# shield.net
KiCad netlist of a schematic drawn in EAGLE
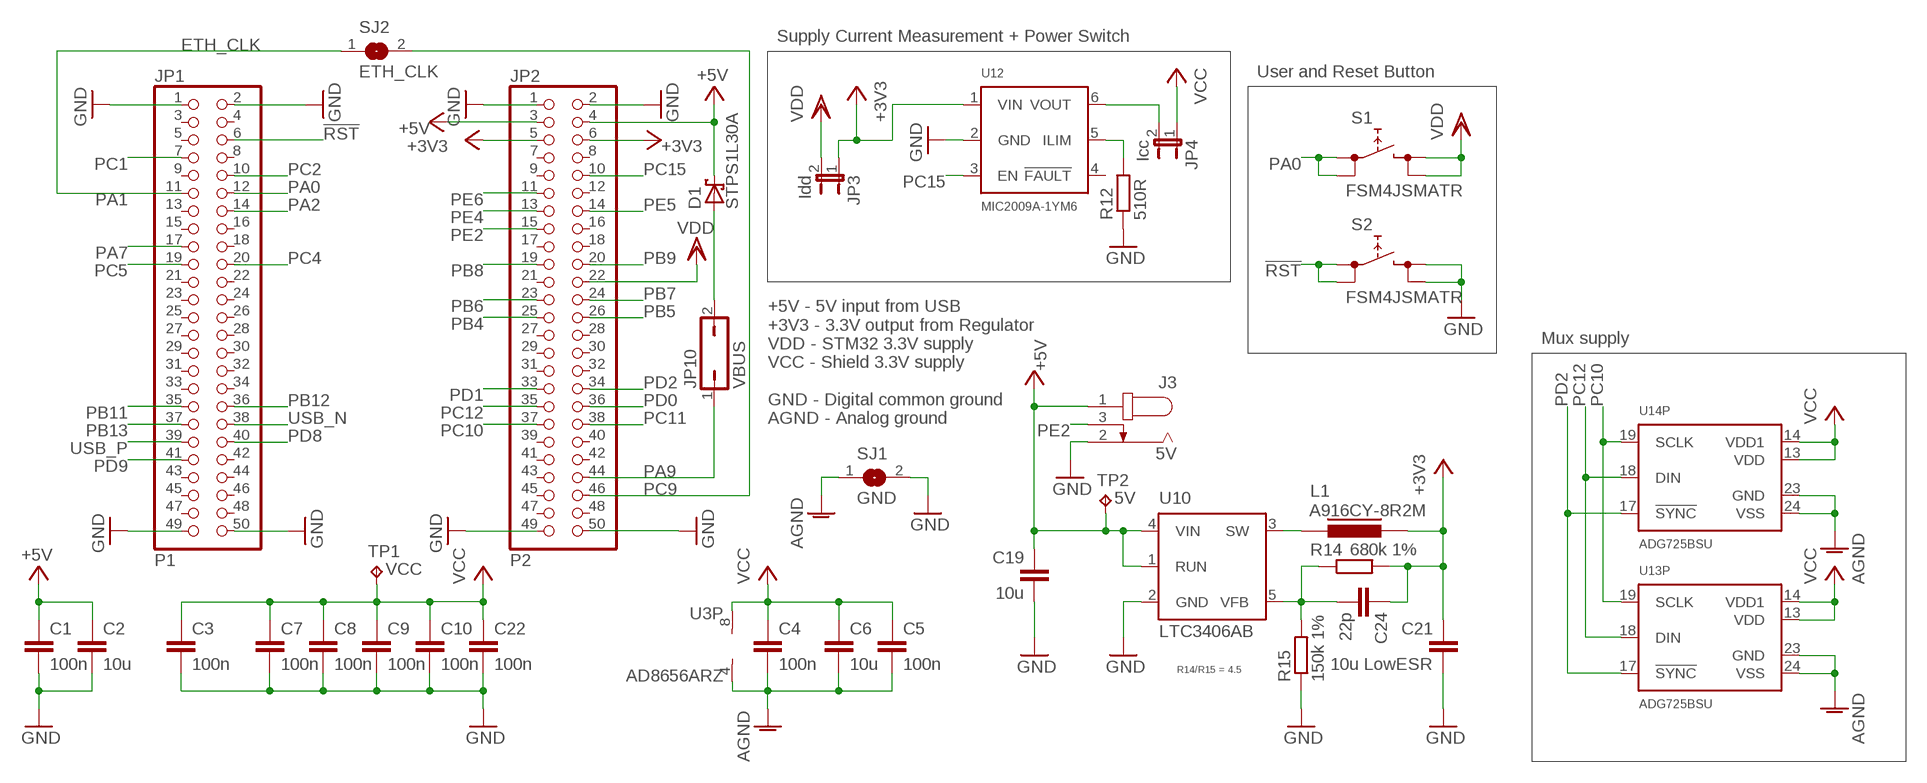
[diagram p0: schematic, sheet 1]
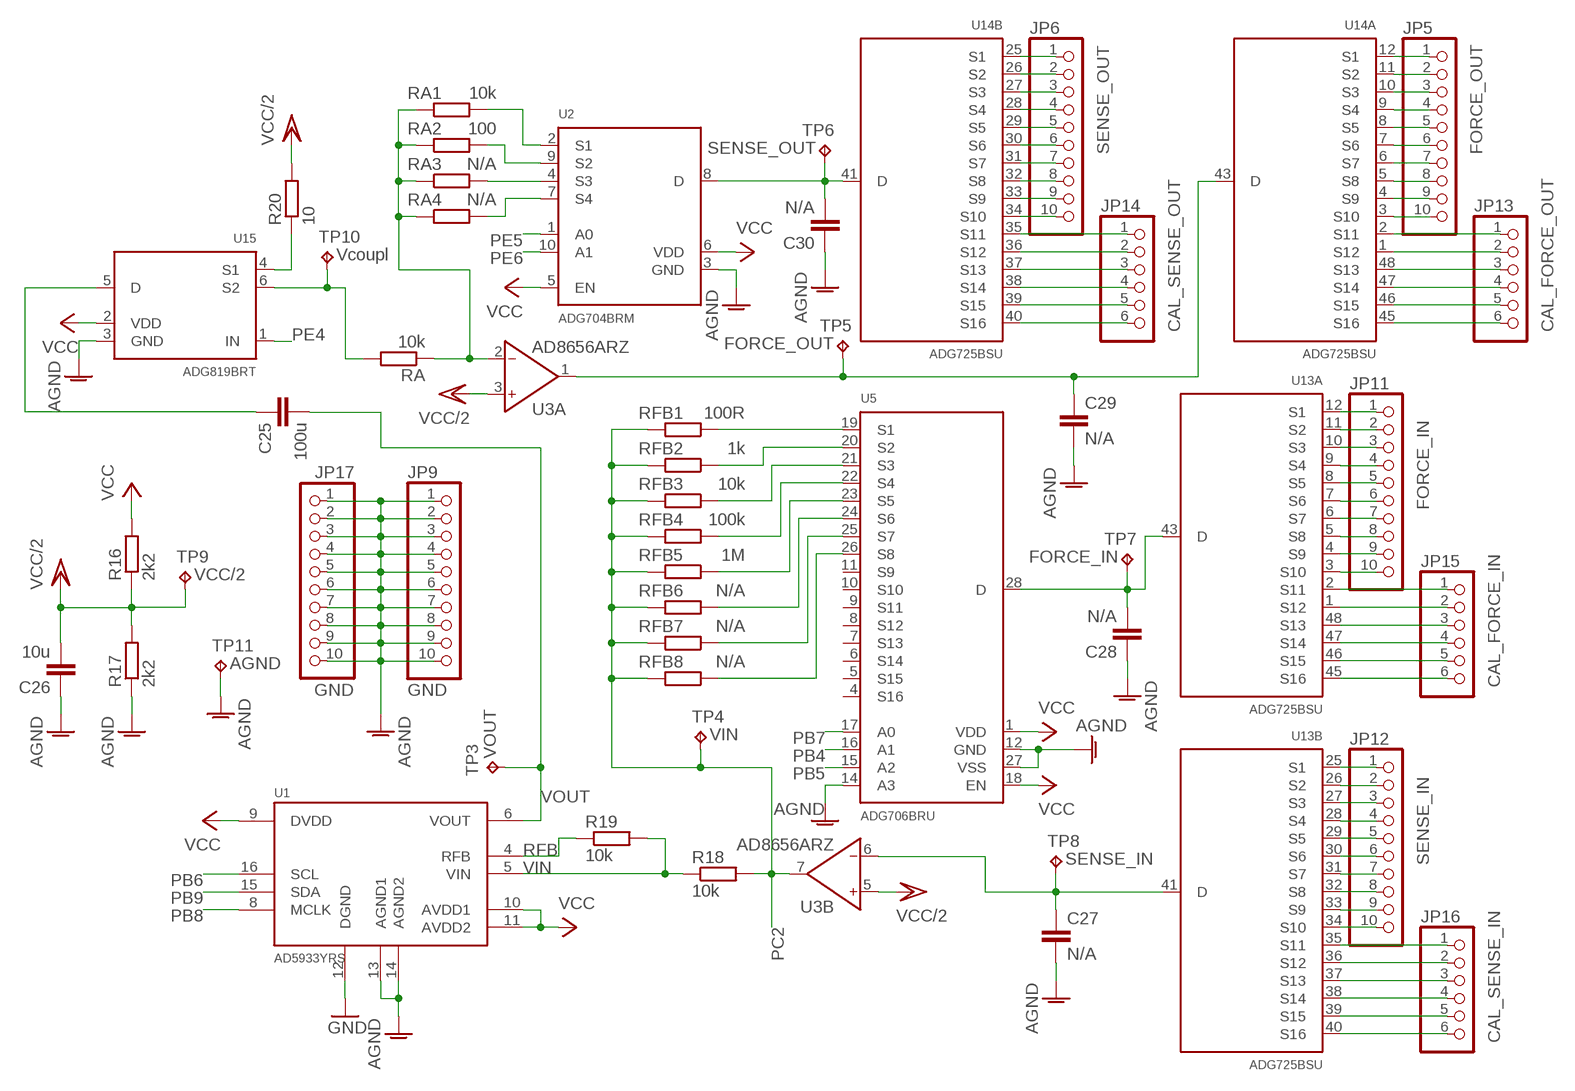
[diagram p1: schematic, sheet 2]
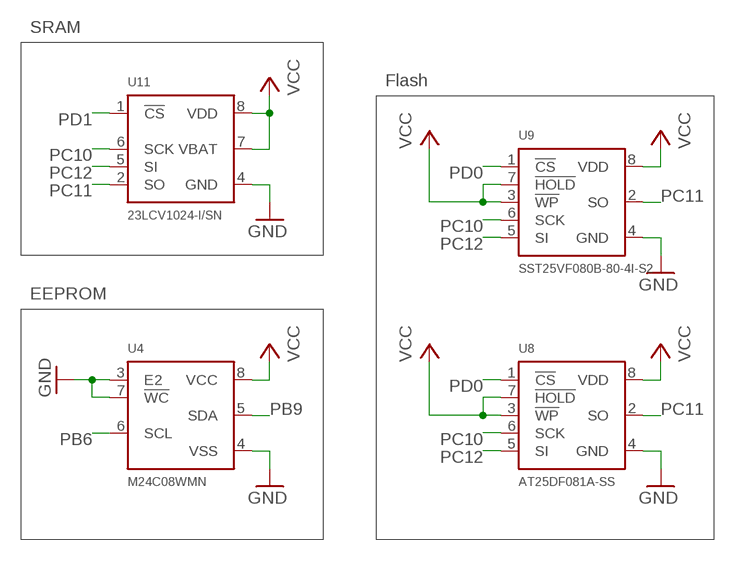
[diagram p2: schematic, sheet 3]
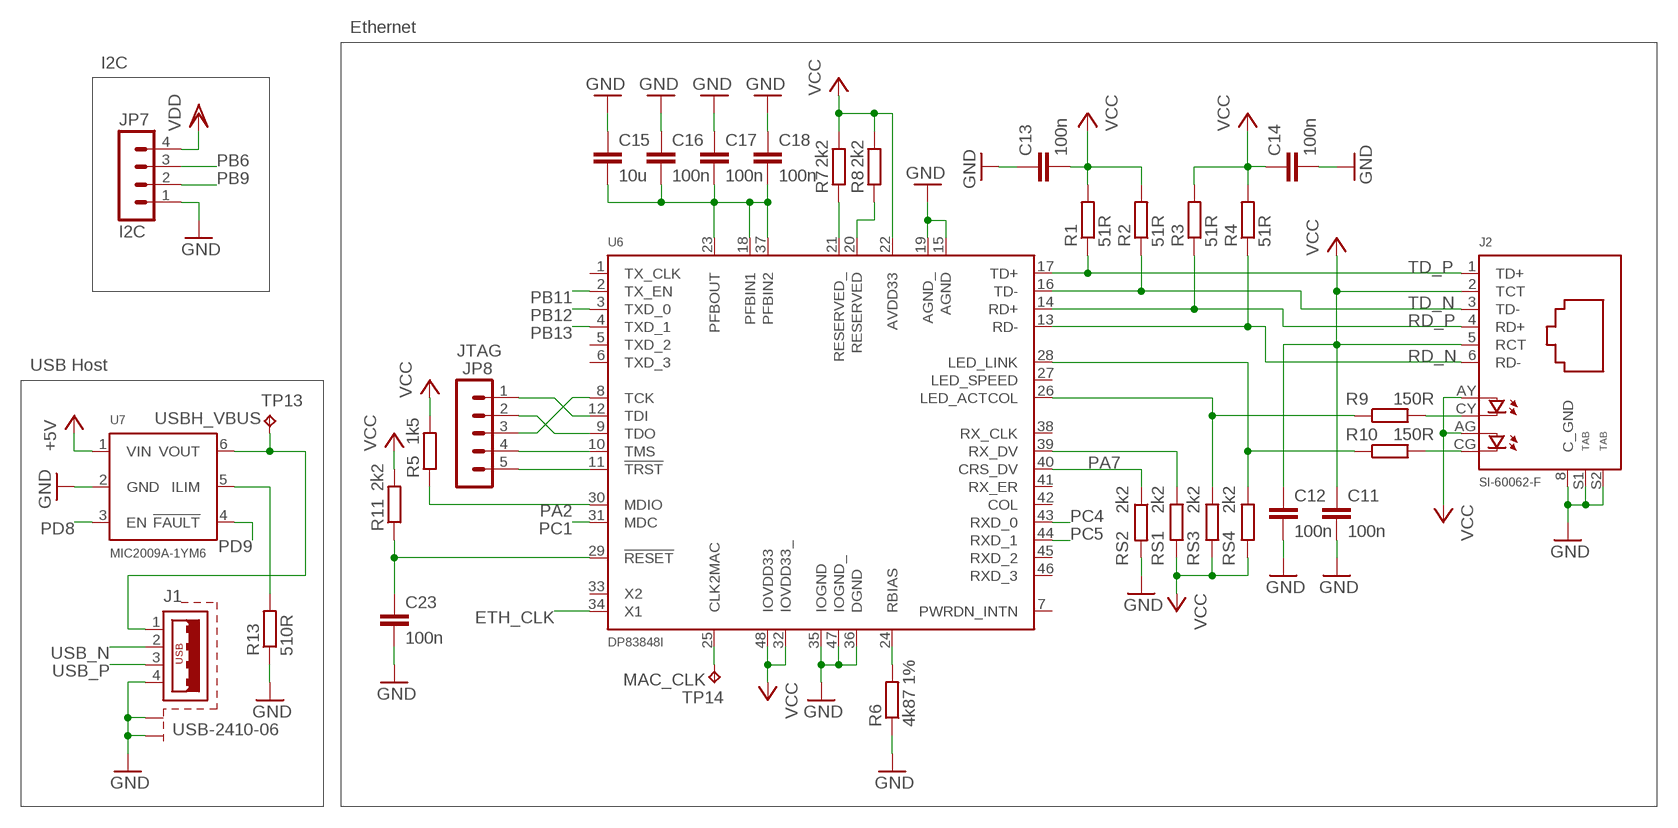
[diagram p3: schematic, sheet 4]

(export (version "E")
  (design (tool "Eeschema 10.0.6"))
  (components
    (comp (ref "C11")
      (value "100n")
      (footprint "eagle-import:C0603")
      (libsource (lib "eagle-import") (part "C-EUC0603"))
    )
    (comp (ref "C12")
      (value "100n")
      (footprint "eagle-import:C0603")
      (libsource (lib "eagle-import") (part "C-EUC0603"))
    )
    (comp (ref "C13")
      (value "100n")
      (footprint "eagle-import:C0603")
      (libsource (lib "eagle-import") (part "C-EUC0603"))
    )
    (comp (ref "C14")
      (value "100n")
      (footprint "eagle-import:C0603")
      (libsource (lib "eagle-import") (part "C-EUC0603"))
    )
    (comp (ref "C15")
      (value "10u")
      (footprint "eagle-import:C0603")
      (libsource (lib "eagle-import") (part "C-EUC0603"))
    )
    (comp (ref "C16")
      (value "100n")
      (footprint "eagle-import:C0603")
      (libsource (lib "eagle-import") (part "C-EUC0603"))
    )
    (comp (ref "C17")
      (value "100n")
      (footprint "eagle-import:C0603")
      (libsource (lib "eagle-import") (part "C-EUC0603"))
    )
    (comp (ref "C18")
      (value "100n")
      (footprint "eagle-import:C0603")
      (libsource (lib "eagle-import") (part "C-EUC0603"))
    )
    (comp (ref "C23")
      (value "100n")
      (footprint "eagle-import:C0603")
      (libsource (lib "eagle-import") (part "C-EUC0603"))
    )
    (comp (ref "J1")
      (value "USB-2410-06")
      (footprint "eagle-import:USB-2410-06")
      (libsource (lib "eagle-import") (part "USB-2410-06"))
    )
    (comp (ref "J2")
      (value "SI-60062-F")
      (footprint "eagle-import:SI-60062-F")
      (libsource (lib "eagle-import") (part "SI-60062-F"))
    )
    (comp (ref "JP7")
      (value "I2C")
      (footprint "eagle-import:MA04-1")
      (libsource (lib "eagle-import") (part "MA04-1"))
    )
    (comp (ref "JP8")
      (value "JTAG")
      (footprint "eagle-import:MA05-1")
      (libsource (lib "eagle-import") (part "MA05-1"))
    )
    (comp (ref "R1")
      (value "51R")
      (footprint "eagle-import:R0603")
      (libsource (lib "eagle-import") (part "R-EU_R0603"))
    )
    (comp (ref "R2")
      (value "51R")
      (footprint "eagle-import:R0603")
      (libsource (lib "eagle-import") (part "R-EU_R0603"))
    )
    (comp (ref "R3")
      (value "51R")
      (footprint "eagle-import:R0603")
      (libsource (lib "eagle-import") (part "R-EU_R0603"))
    )
    (comp (ref "R4")
      (value "51R")
      (footprint "eagle-import:R0603")
      (libsource (lib "eagle-import") (part "R-EU_R0603"))
    )
    (comp (ref "R5")
      (value "1k5")
      (footprint "eagle-import:R0603")
      (libsource (lib "eagle-import") (part "R-EU_R0603"))
    )
    (comp (ref "R6")
      (value "4k87 1%")
      (footprint "eagle-import:R0603")
      (libsource (lib "eagle-import") (part "R-EU_R0603"))
    )
    (comp (ref "R7")
      (value "2k2")
      (footprint "eagle-import:R0603")
      (libsource (lib "eagle-import") (part "R-EU_R0603"))
    )
    (comp (ref "R8")
      (value "2k2")
      (footprint "eagle-import:R0603")
      (libsource (lib "eagle-import") (part "R-EU_R0603"))
    )
    (comp (ref "R9")
      (value "150R")
      (footprint "eagle-import:R0603")
      (libsource (lib "eagle-import") (part "R-EU_R0603"))
    )
    (comp (ref "R10")
      (value "150R")
      (footprint "eagle-import:R0603")
      (libsource (lib "eagle-import") (part "R-EU_R0603"))
    )
    (comp (ref "R11")
      (value "2k2")
      (footprint "eagle-import:R0603")
      (libsource (lib "eagle-import") (part "R-EU_R0603"))
    )
    (comp (ref "R13")
      (value "510R")
      (footprint "eagle-import:R0603")
      (libsource (lib "eagle-import") (part "R-EU_R0603"))
    )
    (comp (ref "RS1")
      (value "2k2")
      (footprint "eagle-import:R0603")
      (libsource (lib "eagle-import") (part "R-EU_R0603"))
    )
    (comp (ref "RS2")
      (value "2k2")
      (footprint "eagle-import:R0603")
      (libsource (lib "eagle-import") (part "R-EU_R0603"))
    )
    (comp (ref "RS3")
      (value "2k2")
      (footprint "eagle-import:R0603")
      (libsource (lib "eagle-import") (part "R-EU_R0603"))
    )
    (comp (ref "RS4")
      (value "2k2")
      (footprint "eagle-import:R0603")
      (libsource (lib "eagle-import") (part "R-EU_R0603"))
    )
    (comp (ref "TP13")
      (value "TPTP20R")
      (footprint "eagle-import:TP20R")
      (fields (field (name "TP_SIGNAL_NAME") "USBH_VBUS"))
      (libsource (lib "eagle-import") (part "TPTP20R"))
    )
    (comp (ref "TP14")
      (value "TPTP20R")
      (footprint "eagle-import:TP20R")
      (fields (field (name "TP_SIGNAL_NAME") "MAC_CLK"))
      (libsource (lib "eagle-import") (part "TPTP20R"))
    )
    (comp (ref "U6")
      (value "DP83848I")
      (footprint "eagle-import:LQFP48")
      (fields (field (name "MPN") "DP83848IVV"))
      (libsource (lib "eagle-import") (part "DP83848I"))
    )
    (comp (ref "U7")
      (value "MIC2009A-1YM6")
      (footprint "eagle-import:SOT23-6")
      (libsource (lib "eagle-import") (part "MIC2009A-1YM6"))
    )
    (comp (ref "U4")
      (value "M24C08WMN")
      (footprint "eagle-import:SO8")
      (libsource (lib "eagle-import") (part "M24C08MNW"))
    )
    (comp (ref "U8")
      (value "AT25DF081A-SS")
      (footprint "eagle-import:SO8")
      (libsource (lib "eagle-import") (part "AT25DF081A-SS"))
    )
    (comp (ref "U9")
      (value "SST25VF080B-80-4I-S2")
      (footprint "eagle-import:SOIC8")
      (libsource (lib "eagle-import") (part "SST25VF080B-S2-80-4I"))
    )
    (comp (ref "U11")
      (value "23LCV1024-I/SN")
      (footprint "eagle-import:SO8")
      (libsource (lib "eagle-import") (part "23LCV1024/SN-I"))
    )
    (comp (ref "C25")
      (value "100u")
      (footprint "eagle-import:C1206")
      (libsource (lib "eagle-import") (part "C-EUC1206"))
    )
    (comp (ref "C26")
      (value "10u")
      (footprint "eagle-import:C0603")
      (libsource (lib "eagle-import") (part "C-EUC0603"))
    )
    (comp (ref "C27")
      (value "N/A")
      (footprint "eagle-import:C0805")
      (libsource (lib "eagle-import") (part "C-EUC0805"))
    )
    (comp (ref "C28")
      (value "N/A")
      (footprint "eagle-import:C0805")
      (libsource (lib "eagle-import") (part "C-EUC0805"))
    )
    (comp (ref "C29")
      (value "N/A")
      (footprint "eagle-import:C0805")
      (libsource (lib "eagle-import") (part "C-EUC0805"))
    )
    (comp (ref "C30")
      (value "N/A")
      (footprint "eagle-import:C0805")
      (libsource (lib "eagle-import") (part "C-EUC0805"))
    )
    (comp (ref "JP5")
      (value "FORCE_OUT")
      (footprint "eagle-import:1X10")
      (libsource (lib "eagle-import") (part "PINHD-1X10"))
    )
    (comp (ref "JP6")
      (value "SENSE_OUT")
      (footprint "eagle-import:1X10")
      (libsource (lib "eagle-import") (part "PINHD-1X10"))
    )
    (comp (ref "JP9")
      (value "GND")
      (footprint "eagle-import:1X10")
      (libsource (lib "eagle-import") (part "PINHD-1X10"))
    )
    (comp (ref "JP11")
      (value "FORCE_IN")
      (footprint "eagle-import:1X10")
      (libsource (lib "eagle-import") (part "PINHD-1X10"))
    )
    (comp (ref "JP12")
      (value "SENSE_IN")
      (footprint "eagle-import:1X10")
      (libsource (lib "eagle-import") (part "PINHD-1X10"))
    )
    (comp (ref "JP13")
      (value "CAL_FORCE_OUT")
      (footprint "eagle-import:1X06")
      (libsource (lib "eagle-import") (part "PINHD-1X6"))
    )
    (comp (ref "JP14")
      (value "CAL_SENSE_OUT")
      (footprint "eagle-import:1X06")
      (libsource (lib "eagle-import") (part "PINHD-1X6"))
    )
    (comp (ref "JP15")
      (value "CAL_FORCE_IN")
      (footprint "eagle-import:1X06")
      (libsource (lib "eagle-import") (part "PINHD-1X6"))
    )
    (comp (ref "JP16")
      (value "CAL_SENSE_IN")
      (footprint "eagle-import:1X06")
      (libsource (lib "eagle-import") (part "PINHD-1X6"))
    )
    (comp (ref "JP17")
      (value "GND")
      (footprint "eagle-import:1X10")
      (libsource (lib "eagle-import") (part "PINHD-1X10"))
    )
    (comp (ref "R16")
      (value "2k2")
      (footprint "eagle-import:R0603")
      (libsource (lib "eagle-import") (part "R-EU_R0603"))
    )
    (comp (ref "R17")
      (value "2k2")
      (footprint "eagle-import:R0603")
      (libsource (lib "eagle-import") (part "R-EU_R0603"))
    )
    (comp (ref "R18")
      (value "10k")
      (footprint "eagle-import:R0603")
      (libsource (lib "eagle-import") (part "R-EU_R0603"))
    )
    (comp (ref "R19")
      (value "10k")
      (footprint "eagle-import:R0603")
      (libsource (lib "eagle-import") (part "R-EU_R0603"))
    )
    (comp (ref "R20")
      (value "10")
      (footprint "eagle-import:R0603")
      (libsource (lib "eagle-import") (part "R-EU_R0603"))
    )
    (comp (ref "RA")
      (value "10k")
      (footprint "eagle-import:R0603")
      (libsource (lib "eagle-import") (part "R-EU_R0603"))
    )
    (comp (ref "RA1")
      (value "10k")
      (footprint "eagle-import:R0603")
      (libsource (lib "eagle-import") (part "R-EU_R0603"))
    )
    (comp (ref "RA2")
      (value "100")
      (footprint "eagle-import:R0603")
      (libsource (lib "eagle-import") (part "R-EU_R0603"))
    )
    (comp (ref "RA3")
      (value "N/A")
      (footprint "eagle-import:R0603")
      (libsource (lib "eagle-import") (part "R-EU_R0603"))
    )
    (comp (ref "RA4")
      (value "N/A")
      (footprint "eagle-import:R0603")
      (libsource (lib "eagle-import") (part "R-EU_R0603"))
    )
    (comp (ref "RFB1")
      (value "100R")
      (footprint "eagle-import:R0603")
      (libsource (lib "eagle-import") (part "R-EU_R0603"))
    )
    (comp (ref "RFB2")
      (value "1k")
      (footprint "eagle-import:R0603")
      (libsource (lib "eagle-import") (part "R-EU_R0603"))
    )
    (comp (ref "RFB3")
      (value "10k")
      (footprint "eagle-import:R0603")
      (libsource (lib "eagle-import") (part "R-EU_R0603"))
    )
    (comp (ref "RFB4")
      (value "100k")
      (footprint "eagle-import:R0603")
      (libsource (lib "eagle-import") (part "R-EU_R0603"))
    )
    (comp (ref "RFB5")
      (value "1M")
      (footprint "eagle-import:R0603")
      (libsource (lib "eagle-import") (part "R-EU_R0603"))
    )
    (comp (ref "RFB6")
      (value "N/A")
      (footprint "eagle-import:R0603")
      (libsource (lib "eagle-import") (part "R-EU_R0603"))
    )
    (comp (ref "RFB7")
      (value "N/A")
      (footprint "eagle-import:R0603")
      (libsource (lib "eagle-import") (part "R-EU_R0603"))
    )
    (comp (ref "RFB8")
      (value "N/A")
      (footprint "eagle-import:R0603")
      (libsource (lib "eagle-import") (part "R-EU_R0603"))
    )
    (comp (ref "TP3")
      (value "TPTP20R")
      (footprint "eagle-import:TP20R")
      (fields (field (name "TP_SIGNAL_NAME") "VOUT"))
      (libsource (lib "eagle-import") (part "TPTP20R"))
    )
    (comp (ref "TP4")
      (value "TPTP20R")
      (footprint "eagle-import:TP20R")
      (fields (field (name "TP_SIGNAL_NAME") "VIN"))
      (libsource (lib "eagle-import") (part "TPTP20R"))
    )
    (comp (ref "TP5")
      (value "TPTP20R")
      (footprint "eagle-import:TP20R")
      (fields (field (name "TP_SIGNAL_NAME") "FORCE_OUT"))
      (libsource (lib "eagle-import") (part "TPTP20R"))
    )
    (comp (ref "TP6")
      (value "TPTP20R")
      (footprint "eagle-import:TP20R")
      (fields (field (name "TP_SIGNAL_NAME") "SENSE_OUT"))
      (libsource (lib "eagle-import") (part "TPTP20R"))
    )
    (comp (ref "TP7")
      (value "TPTP20R")
      (footprint "eagle-import:TP20R")
      (fields (field (name "TP_SIGNAL_NAME") "FORCE_IN"))
      (libsource (lib "eagle-import") (part "TPTP20R"))
    )
    (comp (ref "TP8")
      (value "TPTP20R")
      (footprint "eagle-import:TP20R")
      (fields (field (name "TP_SIGNAL_NAME") "SENSE_IN"))
      (libsource (lib "eagle-import") (part "TPTP20R"))
    )
    (comp (ref "TP9")
      (value "TPTP20R")
      (footprint "eagle-import:TP20R")
      (fields (field (name "TP_SIGNAL_NAME") "VCC/2"))
      (libsource (lib "eagle-import") (part "TPTP20R"))
    )
    (comp (ref "TP10")
      (value "TPTP20R")
      (footprint "eagle-import:TP20R")
      (fields (field (name "TP_SIGNAL_NAME") "Vcoupl"))
      (libsource (lib "eagle-import") (part "TPTP20R"))
    )
    (comp (ref "TP11")
      (value "TPPAD1-13")
      (footprint "eagle-import:P1-13")
      (fields (field (name "TP_SIGNAL_NAME") "AGND"))
      (libsource (lib "eagle-import") (part "TPPAD1-13"))
    )
    (comp (ref "U1")
      (value "AD5933YRS")
      (footprint "eagle-import:SSOP16")
      (libsource (lib "eagle-import") (part "AD5933RSY"))
    )
    (comp (ref "U2")
      (value "ADG704BRM")
      (footprint "eagle-import:MSOP10")
      (libsource (lib "eagle-import") (part "ADG704RMB"))
    )
    (comp (ref "U3")
      (value "AD8656ARZ")
      (footprint "eagle-import:SOIC8")
      (libsource (lib "eagle-import") (part "AD8656ZAR"))
    )
    (comp (ref "U5")
      (value "ADG706BRU")
      (footprint "eagle-import:TSSOP28")
      (libsource (lib "eagle-import") (part "ADG706RUB"))
    )
    (comp (ref "U13")
      (value "ADG725BSU")
      (footprint "eagle-import:TQFP48")
      (libsource (lib "eagle-import") (part "ADG725SUB"))
    )
    (comp (ref "U14")
      (value "ADG725BSU")
      (footprint "eagle-import:TQFP48")
      (libsource (lib "eagle-import") (part "ADG725SUB"))
    )
    (comp (ref "U15")
      (value "ADG819BRT")
      (footprint "eagle-import:SOT23-6")
      (libsource (lib "eagle-import") (part "ADG819RTB"))
    )
    (comp (ref "C1")
      (value "100n")
      (footprint "eagle-import:C0603")
      (libsource (lib "eagle-import") (part "C-EUC0603"))
    )
    (comp (ref "C2")
      (value "10u")
      (footprint "eagle-import:C0603")
      (libsource (lib "eagle-import") (part "C-EUC0603"))
    )
    (comp (ref "C3")
      (value "100n")
      (footprint "eagle-import:C0603")
      (libsource (lib "eagle-import") (part "C-EUC0603"))
    )
    (comp (ref "C4")
      (value "100n")
      (footprint "eagle-import:C0603")
      (libsource (lib "eagle-import") (part "C-EUC0603"))
    )
    (comp (ref "C5")
      (value "100n")
      (footprint "eagle-import:C0603")
      (libsource (lib "eagle-import") (part "C-EUC0603"))
    )
    (comp (ref "C6")
      (value "10u")
      (footprint "eagle-import:C0603")
      (libsource (lib "eagle-import") (part "C-EUC0603"))
    )
    (comp (ref "C7")
      (value "100n")
      (footprint "eagle-import:C0603")
      (libsource (lib "eagle-import") (part "C-EUC0603"))
    )
    (comp (ref "C8")
      (value "100n")
      (footprint "eagle-import:C0603")
      (libsource (lib "eagle-import") (part "C-EUC0603"))
    )
    (comp (ref "C9")
      (value "100n")
      (footprint "eagle-import:C0603")
      (libsource (lib "eagle-import") (part "C-EUC0603"))
    )
    (comp (ref "C10")
      (value "100n")
      (footprint "eagle-import:C0603")
      (libsource (lib "eagle-import") (part "C-EUC0603"))
    )
    (comp (ref "C19")
      (value "10u")
      (footprint "eagle-import:C3216")
      (libsource (lib "eagle-import") (part "C-EUC3216"))
    )
    (comp (ref "C21")
      (value "10u LowESR")
      (footprint "eagle-import:C3216")
      (libsource (lib "eagle-import") (part "C-EUC3216"))
    )
    (comp (ref "C22")
      (value "100n")
      (footprint "eagle-import:C0603")
      (libsource (lib "eagle-import") (part "C-EUC0603"))
    )
    (comp (ref "C24")
      (value "22p")
      (footprint "eagle-import:C0603")
      (libsource (lib "eagle-import") (part "C-EUC0603"))
    )
    (comp (ref "D1")
      (value "STPS1L30A")
      (footprint "eagle-import:DO214AC")
      (libsource (lib "eagle-import") (part "STPS1L30A"))
    )
    (comp (ref "J3")
      (value "5V")
      (footprint "eagle-import:JACK-SMD2.5")
      (libsource (lib "eagle-import") (part "JACK-PLUG-S2.5"))
    )
    (comp (ref "JP1")
      (value "P1")
      (footprint "eagle-import:2X25-F")
      (libsource (lib "eagle-import") (part "PINHD-2X25-F"))
    )
    (comp (ref "JP2")
      (value "P2")
      (footprint "eagle-import:2X25-F")
      (libsource (lib "eagle-import") (part "PINHD-2X25-F"))
    )
    (comp (ref "JP3")
      (value "Idd")
      (footprint "eagle-import:JP1")
      (libsource (lib "eagle-import") (part "JP1E"))
    )
    (comp (ref "JP4")
      (value "Icc")
      (footprint "eagle-import:JP1")
      (libsource (lib "eagle-import") (part "JP1E"))
    )
    (comp (ref "JP10")
      (value "VBUS")
      (footprint "eagle-import:JP1")
      (libsource (lib "eagle-import") (part "JP1Q"))
    )
    (comp (ref "L1")
      (value "A916CY-8R2M")
      (footprint "eagle-import:D63CB")
      (libsource (lib "eagle-import") (part "A916CY-8R2M"))
    )
    (comp (ref "R12")
      (value "510R")
      (footprint "eagle-import:R0603")
      (libsource (lib "eagle-import") (part "R-EU_R0603"))
    )
    (comp (ref "R14")
      (value "680k 1%")
      (footprint "eagle-import:R0603")
      (libsource (lib "eagle-import") (part "R-EU_R0603"))
    )
    (comp (ref "R15")
      (value "150k 1%")
      (footprint "eagle-import:R0603")
      (libsource (lib "eagle-import") (part "R-EU_R0603"))
    )
    (comp (ref "S1")
      (value "FSM4JSMATR")
      (footprint "eagle-import:FSM")
      (libsource (lib "eagle-import") (part "FSM4JSMATR"))
    )
    (comp (ref "S2")
      (value "FSM4JSMATR")
      (footprint "eagle-import:FSM")
      (libsource (lib "eagle-import") (part "FSM4JSMATR"))
    )
    (comp (ref "SJ1")
      (value "GND")
      (footprint "eagle-import:SJ")
      (libsource (lib "eagle-import") (part "SJ"))
    )
    (comp (ref "SJ2")
      (value "ETH_CLK")
      (footprint "eagle-import:SJ")
      (libsource (lib "eagle-import") (part "SJ"))
    )
    (comp (ref "TP1")
      (value "TPTP20R")
      (footprint "eagle-import:TP20R")
      (fields (field (name "TP_SIGNAL_NAME") "VCC"))
      (libsource (lib "eagle-import") (part "TPTP20R"))
    )
    (comp (ref "TP2")
      (value "TPTP20R")
      (footprint "eagle-import:TP20R")
      (fields (field (name "TP_SIGNAL_NAME") "5V"))
      (libsource (lib "eagle-import") (part "TPTP20R"))
    )
    (comp (ref "U10")
      (value "LTC3406AB")
      (footprint "eagle-import:TSOT23-5")
      (libsource (lib "eagle-import") (part "LTC3406AB"))
    )
    (comp (ref "U12")
      (value "MIC2009A-1YM6")
      (footprint "eagle-import:SOT23-6")
      (libsource (lib "eagle-import") (part "MIC2009A-1YM6"))
    )
  )
  (nets
    (net (code "1") (name "+3V3") (class "Default")
      (node (ref "C21") (pin "1") (pinfunction "1_1") (pintype "passive"))
      (node (ref "C24") (pin "1") (pinfunction "1_1") (pintype "passive"))
      (node (ref "JP2") (pin "5") (pinfunction "5_5") (pintype "passive"))
      (node (ref "JP2") (pin "6") (pinfunction "6_6") (pintype "passive"))
      (node (ref "JP3") (pin "1") (pinfunction "1_1") (pintype "passive"))
      (node (ref "L1") (pin "2") (pinfunction "2_2") (pintype "passive"))
      (node (ref "R14") (pin "2") (pinfunction "2_2") (pintype "passive"))
      (node (ref "U12") (pin "1") (pinfunction "VIN_1") (pintype "power_in"))
    )
    (net (code "2") (name "+5V") (class "Default")
      (node (ref "C1") (pin "1") (pinfunction "1_1") (pintype "passive"))
      (node (ref "C19") (pin "1") (pinfunction "1_1") (pintype "passive"))
      (node (ref "C2") (pin "1") (pinfunction "1_1") (pintype "passive"))
      (node (ref "D1") (pin "C") (pinfunction "C_C") (pintype "passive"))
      (node (ref "J3") (pin "1") (pinfunction "1_1") (pintype "passive"))
      (node (ref "JP2") (pin "3") (pinfunction "3_3") (pintype "passive"))
      (node (ref "JP2") (pin "4") (pinfunction "4_4") (pintype "passive"))
      (node (ref "TP2") (pin "TP") (pinfunction "TP_TP") (pintype "input"))
      (node (ref "U10") (pin "1") (pinfunction "RUN_1") (pintype "input"))
      (node (ref "U10") (pin "4") (pinfunction "VIN_4") (pintype "power_in"))
      (node (ref "U7") (pin "1") (pinfunction "VIN_1") (pintype "power_in"))
    )
    (net (code "3") (name "AGND") (class "Default")
      (node (ref "C26") (pin "1") (pinfunction "1_1") (pintype "passive"))
      (node (ref "C27") (pin "2") (pinfunction "2_2") (pintype "passive"))
      (node (ref "C28") (pin "1") (pinfunction "1_1") (pintype "passive"))
      (node (ref "C29") (pin "2") (pinfunction "2_2") (pintype "passive"))
      (node (ref "C30") (pin "1") (pinfunction "1_1") (pintype "passive"))
      (node (ref "C4") (pin "2") (pinfunction "2_2") (pintype "passive"))
      (node (ref "C5") (pin "2") (pinfunction "2_2") (pintype "passive"))
      (node (ref "C6") (pin "2") (pinfunction "2_2") (pintype "passive"))
      (node (ref "JP17") (pin "1") (pinfunction "1_1") (pintype "passive"))
      (node (ref "JP17") (pin "10") (pinfunction "10_10") (pintype "passive"))
      (node (ref "JP17") (pin "2") (pinfunction "2_2") (pintype "passive"))
      (node (ref "JP17") (pin "3") (pinfunction "3_3") (pintype "passive"))
      (node (ref "JP17") (pin "4") (pinfunction "4_4") (pintype "passive"))
      (node (ref "JP17") (pin "5") (pinfunction "5_5") (pintype "passive"))
      (node (ref "JP17") (pin "6") (pinfunction "6_6") (pintype "passive"))
      (node (ref "JP17") (pin "7") (pinfunction "7_7") (pintype "passive"))
      (node (ref "JP17") (pin "8") (pinfunction "8_8") (pintype "passive"))
      (node (ref "JP17") (pin "9") (pinfunction "9_9") (pintype "passive"))
      (node (ref "JP9") (pin "1") (pinfunction "1_1") (pintype "passive"))
      (node (ref "JP9") (pin "10") (pinfunction "10_10") (pintype "passive"))
      (node (ref "JP9") (pin "2") (pinfunction "2_2") (pintype "passive"))
      (node (ref "JP9") (pin "3") (pinfunction "3_3") (pintype "passive"))
      (node (ref "JP9") (pin "4") (pinfunction "4_4") (pintype "passive"))
      (node (ref "JP9") (pin "5") (pinfunction "5_5") (pintype "passive"))
      (node (ref "JP9") (pin "6") (pinfunction "6_6") (pintype "passive"))
      (node (ref "JP9") (pin "7") (pinfunction "7_7") (pintype "passive"))
      (node (ref "JP9") (pin "8") (pinfunction "8_8") (pintype "passive"))
      (node (ref "JP9") (pin "9") (pinfunction "9_9") (pintype "passive"))
      (node (ref "R17") (pin "1") (pinfunction "1_1") (pintype "passive"))
      (node (ref "SJ1") (pin "1") (pinfunction "1_1") (pintype "passive"))
      (node (ref "TP11") (pin "TP") (pinfunction "TP_TP") (pintype "input"))
      (node (ref "U1") (pin "13") (pinfunction "AGND1_13") (pintype "bidirectional"))
      (node (ref "U1") (pin "14") (pinfunction "AGND2_14") (pintype "bidirectional"))
      (node (ref "U13") (pin "23") (pinfunction "GND_23") (pintype "power_in"))
      (node (ref "U13") (pin "24") (pinfunction "VSS_24") (pintype "power_in"))
      (node (ref "U14") (pin "23") (pinfunction "GND_23") (pintype "power_in"))
      (node (ref "U14") (pin "24") (pinfunction "VSS_24") (pintype "power_in"))
      (node (ref "U15") (pin "3") (pinfunction "GND_3") (pintype "power_in"))
      (node (ref "U2") (pin "3") (pinfunction "GND_3") (pintype "power_in"))
      (node (ref "U3") (pin "4") (pinfunction "V-_4") (pintype "power_in"))
      (node (ref "U5") (pin "12") (pinfunction "GND_12") (pintype "power_in"))
      (node (ref "U5") (pin "14") (pinfunction "A3_14") (pintype "input"))
      (node (ref "U5") (pin "27") (pinfunction "VSS_27") (pintype "power_in"))
    )
    (net (code "4") (name "ETH_CLK") (class "Default")
      (node (ref "JP1") (pin "11") (pinfunction "11_11") (pintype "passive"))
      (node (ref "SJ2") (pin "1") (pinfunction "1_1") (pintype "passive"))
      (node (ref "U6") (pin "34") (pinfunction "X1_34") (pintype "input"))
    )
    (net (code "5") (name "GND") (class "Default")
      (node (ref "C1") (pin "2") (pinfunction "2_2") (pintype "passive"))
      (node (ref "C10") (pin "2") (pinfunction "2_2") (pintype "passive"))
      (node (ref "C11") (pin "2") (pinfunction "2_2") (pintype "passive"))
      (node (ref "C12") (pin "2") (pinfunction "2_2") (pintype "passive"))
      (node (ref "C13") (pin "1") (pinfunction "1_1") (pintype "passive"))
      (node (ref "C14") (pin "2") (pinfunction "2_2") (pintype "passive"))
      (node (ref "C15") (pin "1") (pinfunction "1_1") (pintype "passive"))
      (node (ref "C16") (pin "1") (pinfunction "1_1") (pintype "passive"))
      (node (ref "C17") (pin "1") (pinfunction "1_1") (pintype "passive"))
      (node (ref "C18") (pin "1") (pinfunction "1_1") (pintype "passive"))
      (node (ref "C19") (pin "2") (pinfunction "2_2") (pintype "passive"))
      (node (ref "C2") (pin "2") (pinfunction "2_2") (pintype "passive"))
      (node (ref "C21") (pin "2") (pinfunction "2_2") (pintype "passive"))
      (node (ref "C22") (pin "2") (pinfunction "2_2") (pintype "passive"))
      (node (ref "C23") (pin "2") (pinfunction "2_2") (pintype "passive"))
      (node (ref "C3") (pin "2") (pinfunction "2_2") (pintype "passive"))
      (node (ref "C7") (pin "2") (pinfunction "2_2") (pintype "passive"))
      (node (ref "C8") (pin "2") (pinfunction "2_2") (pintype "passive"))
      (node (ref "C9") (pin "2") (pinfunction "2_2") (pintype "passive"))
      (node (ref "J1") (pin "4") (pinfunction "GND_4") (pintype "passive"))
      (node (ref "J1") (pin "S1") (pinfunction "S1_S1") (pintype "passive"))
      (node (ref "J1") (pin "S2") (pinfunction "S2_S2") (pintype "passive"))
      (node (ref "J2") (pin "8") (pinfunction "C_GND_8") (pintype "passive"))
      (node (ref "J2") (pin "S1") (pinfunction "TAB1_S1") (pintype "passive"))
      (node (ref "J2") (pin "S2") (pinfunction "TAB2_S2") (pintype "passive"))
      (node (ref "J3") (pin "2") (pinfunction "3_2") (pintype "passive"))
      (node (ref "JP1") (pin "1") (pinfunction "1_1") (pintype "passive"))
      (node (ref "JP1") (pin "2") (pinfunction "2_2") (pintype "passive"))
      (node (ref "JP1") (pin "49") (pinfunction "49_49") (pintype "passive"))
      (node (ref "JP1") (pin "50") (pinfunction "50_50") (pintype "passive"))
      (node (ref "JP2") (pin "1") (pinfunction "1_1") (pintype "passive"))
      (node (ref "JP2") (pin "2") (pinfunction "2_2") (pintype "passive"))
      (node (ref "JP2") (pin "49") (pinfunction "49_49") (pintype "passive"))
      (node (ref "JP2") (pin "50") (pinfunction "50_50") (pintype "passive"))
      (node (ref "JP7") (pin "1") (pinfunction "1_1") (pintype "passive"))
      (node (ref "R12") (pin "1") (pinfunction "1_1") (pintype "passive"))
      (node (ref "R13") (pin "1") (pinfunction "1_1") (pintype "passive"))
      (node (ref "R15") (pin "1") (pinfunction "1_1") (pintype "passive"))
      (node (ref "R6") (pin "1") (pinfunction "1_1") (pintype "passive"))
      (node (ref "RS2") (pin "2") (pinfunction "2_2") (pintype "passive"))
      (node (ref "S2") (pin "3") (pinfunction "1_3") (pintype "passive"))
      (node (ref "S2") (pin "4") (pinfunction "1_4") (pintype "passive"))
      (node (ref "SJ1") (pin "2") (pinfunction "2_2") (pintype "passive"))
      (node (ref "U1") (pin "12") (pinfunction "DGND_12") (pintype "bidirectional"))
      (node (ref "U10") (pin "2") (pinfunction "GND_2") (pintype "power_in"))
      (node (ref "U11") (pin "4") (pinfunction "GND_4") (pintype "power_in"))
      (node (ref "U12") (pin "2") (pinfunction "GND_2") (pintype "power_in"))
      (node (ref "U4") (pin "3") (pinfunction "E2_3") (pintype "input"))
      (node (ref "U4") (pin "4") (pinfunction "VSS_4") (pintype "power_in"))
      (node (ref "U4") (pin "7") (pinfunction "~{WC}_7") (pintype "input"))
      (node (ref "U6") (pin "15") (pinfunction "AGND_15") (pintype "power_in"))
      (node (ref "U6") (pin "19") (pinfunction "AGND__19") (pintype "power_in"))
      (node (ref "U6") (pin "35") (pinfunction "IOGND_35") (pintype "power_in"))
      (node (ref "U6") (pin "36") (pinfunction "DGND_36") (pintype "power_in"))
      (node (ref "U6") (pin "47") (pinfunction "IOGND__47") (pintype "power_in"))
      (node (ref "U7") (pin "2") (pinfunction "GND_2") (pintype "power_in"))
      (node (ref "U8") (pin "4") (pinfunction "GND_4") (pintype "power_in"))
      (node (ref "U9") (pin "4") (pinfunction "GND_4") (pintype "power_in"))
    )
    (net (code "6") (name "Net-(D1-PadA)") (class "Default")
      (node (ref "D1") (pin "A") (pinfunction "A_A") (pintype "passive"))
      (node (ref "JP10") (pin "2") (pinfunction "2_2") (pintype "passive"))
    )
    (net (code "7") (name "Net-(J1-VCC)") (class "Default")
      (node (ref "J1") (pin "1") (pinfunction "VCC_1") (pintype "passive"))
      (node (ref "TP13") (pin "TP") (pinfunction "TP_TP") (pintype "input"))
      (node (ref "U7") (pin "6") (pinfunction "VOUT_6") (pintype "power_in"))
    )
    (net (code "8") (name "Net-(J2-PadCG)") (class "Default")
      (node (ref "J2") (pin "CG") (pinfunction "CG_CG") (pintype "passive"))
      (node (ref "R10") (pin "2") (pinfunction "2_2") (pintype "passive"))
    )
    (net (code "9") (name "Net-(J2-PadCY)") (class "Default")
      (node (ref "J2") (pin "CY") (pinfunction "CY_CY") (pintype "passive"))
      (node (ref "R9") (pin "2") (pinfunction "2_2") (pintype "passive"))
    )
    (net (code "10") (name "Net-(U2-S1)") (class "Default")
      (node (ref "RA1") (pin "2") (pinfunction "2_2") (pintype "passive"))
      (node (ref "U2") (pin "2") (pinfunction "S1_2") (pintype "bidirectional"))
    )
    (net (code "11") (name "Net-(U2-S2)") (class "Default")
      (node (ref "RA2") (pin "2") (pinfunction "2_2") (pintype "passive"))
      (node (ref "U2") (pin "9") (pinfunction "S2_9") (pintype "bidirectional"))
    )
    (net (code "12") (name "Net-(U2-S3)") (class "Default")
      (node (ref "RA3") (pin "2") (pinfunction "2_2") (pintype "passive"))
      (node (ref "U2") (pin "4") (pinfunction "S3_4") (pintype "bidirectional"))
    )
    (net (code "13") (name "Net-(U2-S4)") (class "Default")
      (node (ref "RA4") (pin "2") (pinfunction "2_2") (pintype "passive"))
      (node (ref "U2") (pin "7") (pinfunction "S4_7") (pintype "bidirectional"))
    )
    (net (code "14") (name "Net-(U3A-IN-)") (class "Default")
      (node (ref "RA") (pin "1") (pinfunction "1_1") (pintype "passive"))
      (node (ref "RA1") (pin "1") (pinfunction "1_1") (pintype "passive"))
      (node (ref "RA2") (pin "1") (pinfunction "1_1") (pintype "passive"))
      (node (ref "RA3") (pin "1") (pinfunction "1_1") (pintype "passive"))
      (node (ref "RA4") (pin "1") (pinfunction "1_1") (pintype "passive"))
      (node (ref "U3") (pin "2") (pinfunction "IN-_2") (pintype "input"))
    )
    (net (code "15") (name "Net-(U5-S1)") (class "Default")
      (node (ref "RFB1") (pin "1") (pinfunction "1_1") (pintype "passive"))
      (node (ref "U5") (pin "19") (pinfunction "S1_19") (pintype "bidirectional"))
    )
    (net (code "16") (name "Net-(U5-S2)") (class "Default")
      (node (ref "RFB2") (pin "1") (pinfunction "1_1") (pintype "passive"))
      (node (ref "U5") (pin "20") (pinfunction "S2_20") (pintype "bidirectional"))
    )
    (net (code "17") (name "Net-(U5-S3)") (class "Default")
      (node (ref "RFB3") (pin "1") (pinfunction "1_1") (pintype "passive"))
      (node (ref "U5") (pin "21") (pinfunction "S3_21") (pintype "bidirectional"))
    )
    (net (code "18") (name "Net-(U5-S4)") (class "Default")
      (node (ref "RFB4") (pin "1") (pinfunction "1_1") (pintype "passive"))
      (node (ref "U5") (pin "22") (pinfunction "S4_22") (pintype "bidirectional"))
    )
    (net (code "19") (name "Net-(U5-S5)") (class "Default")
      (node (ref "RFB5") (pin "1") (pinfunction "1_1") (pintype "passive"))
      (node (ref "U5") (pin "23") (pinfunction "S5_23") (pintype "bidirectional"))
    )
    (net (code "20") (name "Net-(U5-S6)") (class "Default")
      (node (ref "RFB6") (pin "1") (pinfunction "1_1") (pintype "passive"))
      (node (ref "U5") (pin "24") (pinfunction "S6_24") (pintype "bidirectional"))
    )
    (net (code "21") (name "Net-(U5-S7)") (class "Default")
      (node (ref "RFB7") (pin "1") (pinfunction "1_1") (pintype "passive"))
      (node (ref "U5") (pin "25") (pinfunction "S7_25") (pintype "bidirectional"))
    )
    (net (code "22") (name "Net-(U5-S8)") (class "Default")
      (node (ref "RFB8") (pin "1") (pinfunction "1_1") (pintype "passive"))
      (node (ref "U5") (pin "26") (pinfunction "S8_26") (pintype "bidirectional"))
    )
    (net (code "23") (name "Net-(U6-CLK2MAC)") (class "Default")
      (node (ref "TP14") (pin "TP") (pinfunction "TP_TP") (pintype "input"))
      (node (ref "U6") (pin "25") (pinfunction "CLK2MAC_25") (pintype "output"))
    )
    (net (code "24") (name "Net-(U6-LED_ACTCOL)") (class "Default")
      (node (ref "R9") (pin "1") (pinfunction "1_1") (pintype "passive"))
      (node (ref "RS3") (pin "2") (pinfunction "2_2") (pintype "passive"))
      (node (ref "U6") (pin "26") (pinfunction "LED_ACTCOL_26") (pintype "output"))
    )
    (net (code "25") (name "Net-(U6-LED_LINK)") (class "Default")
      (node (ref "R10") (pin "1") (pinfunction "1_1") (pintype "passive"))
      (node (ref "RS4") (pin "2") (pinfunction "2_2") (pintype "passive"))
      (node (ref "U6") (pin "28") (pinfunction "LED_LINK_28") (pintype "output"))
    )
    (net (code "26") (name "Net-(U6-PFBIN1)") (class "Default")
      (node (ref "C15") (pin "2") (pinfunction "2_2") (pintype "passive"))
      (node (ref "C16") (pin "2") (pinfunction "2_2") (pintype "passive"))
      (node (ref "C17") (pin "2") (pinfunction "2_2") (pintype "passive"))
      (node (ref "C18") (pin "2") (pinfunction "2_2") (pintype "passive"))
      (node (ref "U6") (pin "18") (pinfunction "PFBIN1_18") (pintype "input"))
      (node (ref "U6") (pin "23") (pinfunction "PFBOUT_23") (pintype "output"))
      (node (ref "U6") (pin "37") (pinfunction "PFBIN2_37") (pintype "input"))
    )
    (net (code "27") (name "Net-(U6-RBIAS)") (class "Default")
      (node (ref "R6") (pin "2") (pinfunction "2_2") (pintype "passive"))
      (node (ref "U6") (pin "24") (pinfunction "RBIAS_24") (pintype "bidirectional"))
    )
    (net (code "28") (name "Net-(U6-RESERVED)") (class "Default")
      (node (ref "R8") (pin "1") (pinfunction "1_1") (pintype "passive"))
      (node (ref "U6") (pin "20") (pinfunction "RESERVED_20") (pintype "input"))
    )
    (net (code "29") (name "Net-(U6-RESERVED_)") (class "Default")
      (node (ref "R7") (pin "1") (pinfunction "1_1") (pintype "passive"))
      (node (ref "U6") (pin "21") (pinfunction "RESERVED__21") (pintype "input"))
    )
    (net (code "30") (name "Net-(U6-RX_DV)") (class "Default")
      (node (ref "RS1") (pin "2") (pinfunction "2_2") (pintype "passive"))
      (node (ref "U6") (pin "39") (pinfunction "RX_DV_39") (pintype "output"))
    )
    (net (code "31") (name "Net-(U6-TCK)") (class "Default")
      (node (ref "JP8") (pin "3") (pinfunction "3_3") (pintype "passive"))
      (node (ref "U6") (pin "8") (pinfunction "TCK_8") (pintype "input"))
    )
    (net (code "32") (name "Net-(U6-TDI)") (class "Default")
      (node (ref "JP8") (pin "1") (pinfunction "1_1") (pintype "passive"))
      (node (ref "U6") (pin "12") (pinfunction "TDI_12") (pintype "input"))
    )
    (net (code "33") (name "Net-(U6-TDO)") (class "Default")
      (node (ref "JP8") (pin "2") (pinfunction "2_2") (pintype "passive"))
      (node (ref "U6") (pin "9") (pinfunction "TDO_9") (pintype "output"))
    )
    (net (code "34") (name "Net-(U6-TMS)") (class "Default")
      (node (ref "JP8") (pin "4") (pinfunction "4_4") (pintype "passive"))
      (node (ref "U6") (pin "10") (pinfunction "TMS_10") (pintype "input"))
    )
    (net (code "35") (name "Net-(U6-~{RESET})") (class "Default")
      (node (ref "C23") (pin "1") (pinfunction "1_1") (pintype "passive"))
      (node (ref "R11") (pin "1") (pinfunction "1_1") (pintype "passive"))
      (node (ref "U6") (pin "29") (pinfunction "~{RESET}_29") (pintype "input"))
    )
    (net (code "36") (name "Net-(U6-~{TRST})") (class "Default")
      (node (ref "JP8") (pin "5") (pinfunction "5_5") (pintype "passive"))
      (node (ref "U6") (pin "11") (pinfunction "~{TRST}_11") (pintype "input"))
    )
    (net (code "37") (name "Net-(U7-ILIM)") (class "Default")
      (node (ref "R13") (pin "2") (pinfunction "2_2") (pintype "passive"))
      (node (ref "U7") (pin "5") (pinfunction "ILIM_5") (pintype "passive"))
    )
    (net (code "38") (name "Net-(U10-SW)") (class "Default")
      (node (ref "L1") (pin "1") (pinfunction "1_1") (pintype "passive"))
      (node (ref "U10") (pin "3") (pinfunction "SW_3") (pintype "passive"))
    )
    (net (code "39") (name "Net-(U10-VFB)") (class "Default")
      (node (ref "C24") (pin "2") (pinfunction "2_2") (pintype "passive"))
      (node (ref "R14") (pin "1") (pinfunction "1_1") (pintype "passive"))
      (node (ref "R15") (pin "2") (pinfunction "2_2") (pintype "passive"))
      (node (ref "U10") (pin "5") (pinfunction "VFB_5") (pintype "input"))
    )
    (net (code "40") (name "Net-(U12-ILIM)") (class "Default")
      (node (ref "R12") (pin "2") (pinfunction "2_2") (pintype "passive"))
      (node (ref "U12") (pin "5") (pinfunction "ILIM_5") (pintype "passive"))
    )
    (net (code "41") (name "Net-(U12-VOUT)") (class "Default")
      (node (ref "JP4") (pin "2") (pinfunction "2_2") (pintype "passive"))
      (node (ref "U12") (pin "6") (pinfunction "VOUT_6") (pintype "power_in"))
    )
    (net (code "42") (name "Net-(U13A-D)") (class "Default")
      (node (ref "C28") (pin "2") (pinfunction "2_2") (pintype "passive"))
      (node (ref "TP7") (pin "TP") (pinfunction "TP_TP") (pintype "input"))
      (node (ref "U13") (pin "43") (pinfunction "D_43") (pintype "bidirectional"))
      (node (ref "U5") (pin "28") (pinfunction "D_28") (pintype "bidirectional"))
    )
    (net (code "43") (name "Net-(U13A-S1)") (class "Default")
      (node (ref "JP11") (pin "1") (pinfunction "1_1") (pintype "passive"))
      (node (ref "U13") (pin "12") (pinfunction "S1_12") (pintype "bidirectional"))
    )
    (net (code "44") (name "Net-(U13A-S2)") (class "Default")
      (node (ref "JP11") (pin "2") (pinfunction "2_2") (pintype "passive"))
      (node (ref "U13") (pin "11") (pinfunction "S2_11") (pintype "bidirectional"))
    )
    (net (code "45") (name "Net-(U13A-S3)") (class "Default")
      (node (ref "JP11") (pin "3") (pinfunction "3_3") (pintype "passive"))
      (node (ref "U13") (pin "10") (pinfunction "S3_10") (pintype "bidirectional"))
    )
    (net (code "46") (name "Net-(U13A-S4)") (class "Default")
      (node (ref "JP11") (pin "4") (pinfunction "4_4") (pintype "passive"))
      (node (ref "U13") (pin "9") (pinfunction "S4_9") (pintype "bidirectional"))
    )
    (net (code "47") (name "Net-(U13A-S5)") (class "Default")
      (node (ref "JP11") (pin "5") (pinfunction "5_5") (pintype "passive"))
      (node (ref "U13") (pin "8") (pinfunction "S5_8") (pintype "bidirectional"))
    )
    (net (code "48") (name "Net-(U13A-S6)") (class "Default")
      (node (ref "JP11") (pin "6") (pinfunction "6_6") (pintype "passive"))
      (node (ref "U13") (pin "7") (pinfunction "S6_7") (pintype "bidirectional"))
    )
    (net (code "49") (name "Net-(U13A-S7)") (class "Default")
      (node (ref "JP11") (pin "7") (pinfunction "7_7") (pintype "passive"))
      (node (ref "U13") (pin "6") (pinfunction "S7_6") (pintype "bidirectional"))
    )
    (net (code "50") (name "Net-(U13A-S8)") (class "Default")
      (node (ref "JP11") (pin "8") (pinfunction "8_8") (pintype "passive"))
      (node (ref "U13") (pin "5") (pinfunction "S8_5") (pintype "bidirectional"))
    )
    (net (code "51") (name "Net-(U13A-S9)") (class "Default")
      (node (ref "JP11") (pin "9") (pinfunction "9_9") (pintype "passive"))
      (node (ref "U13") (pin "4") (pinfunction "S9_4") (pintype "bidirectional"))
    )
    (net (code "52") (name "Net-(U13A-S10)") (class "Default")
      (node (ref "JP11") (pin "10") (pinfunction "10_10") (pintype "passive"))
      (node (ref "U13") (pin "3") (pinfunction "S10_3") (pintype "bidirectional"))
    )
    (net (code "53") (name "Net-(U13A-S11)") (class "Default")
      (node (ref "JP15") (pin "1") (pinfunction "1_1") (pintype "passive"))
      (node (ref "U13") (pin "2") (pinfunction "S11_2") (pintype "bidirectional"))
    )
    (net (code "54") (name "Net-(U13A-S12)") (class "Default")
      (node (ref "JP15") (pin "2") (pinfunction "2_2") (pintype "passive"))
      (node (ref "U13") (pin "1") (pinfunction "S12_1") (pintype "bidirectional"))
    )
    (net (code "55") (name "Net-(U13A-S13)") (class "Default")
      (node (ref "JP15") (pin "3") (pinfunction "3_3") (pintype "passive"))
      (node (ref "U13") (pin "48") (pinfunction "S13_48") (pintype "bidirectional"))
    )
    (net (code "56") (name "Net-(U13A-S14)") (class "Default")
      (node (ref "JP15") (pin "4") (pinfunction "4_4") (pintype "passive"))
      (node (ref "U13") (pin "47") (pinfunction "S14_47") (pintype "bidirectional"))
    )
    (net (code "57") (name "Net-(U13A-S15)") (class "Default")
      (node (ref "JP15") (pin "5") (pinfunction "5_5") (pintype "passive"))
      (node (ref "U13") (pin "46") (pinfunction "S15_46") (pintype "bidirectional"))
    )
    (net (code "58") (name "Net-(U13A-S16)") (class "Default")
      (node (ref "JP15") (pin "6") (pinfunction "6_6") (pintype "passive"))
      (node (ref "U13") (pin "45") (pinfunction "S16_45") (pintype "bidirectional"))
    )
    (net (code "59") (name "Net-(U13B-D)") (class "Default")
      (node (ref "C27") (pin "1") (pinfunction "1_1") (pintype "passive"))
      (node (ref "TP8") (pin "TP") (pinfunction "TP_TP") (pintype "input"))
      (node (ref "U13") (pin "41") (pinfunction "D_41") (pintype "bidirectional"))
      (node (ref "U3") (pin "6") (pinfunction "IN-_6") (pintype "input"))
    )
    (net (code "60") (name "Net-(U13B-S1)") (class "Default")
      (node (ref "JP12") (pin "1") (pinfunction "1_1") (pintype "passive"))
      (node (ref "U13") (pin "25") (pinfunction "S1_25") (pintype "bidirectional"))
    )
    (net (code "61") (name "Net-(U13B-S2)") (class "Default")
      (node (ref "JP12") (pin "2") (pinfunction "2_2") (pintype "passive"))
      (node (ref "U13") (pin "26") (pinfunction "S2_26") (pintype "bidirectional"))
    )
    (net (code "62") (name "Net-(U13B-S3)") (class "Default")
      (node (ref "JP12") (pin "3") (pinfunction "3_3") (pintype "passive"))
      (node (ref "U13") (pin "27") (pinfunction "S3_27") (pintype "bidirectional"))
    )
    (net (code "63") (name "Net-(U13B-S4)") (class "Default")
      (node (ref "JP12") (pin "4") (pinfunction "4_4") (pintype "passive"))
      (node (ref "U13") (pin "28") (pinfunction "S4_28") (pintype "bidirectional"))
    )
    (net (code "64") (name "Net-(U13B-S5)") (class "Default")
      (node (ref "JP12") (pin "5") (pinfunction "5_5") (pintype "passive"))
      (node (ref "U13") (pin "29") (pinfunction "S5_29") (pintype "bidirectional"))
    )
    (net (code "65") (name "Net-(U13B-S6)") (class "Default")
      (node (ref "JP12") (pin "6") (pinfunction "6_6") (pintype "passive"))
      (node (ref "U13") (pin "30") (pinfunction "S6_30") (pintype "bidirectional"))
    )
    (net (code "66") (name "Net-(U13B-S7)") (class "Default")
      (node (ref "JP12") (pin "7") (pinfunction "7_7") (pintype "passive"))
      (node (ref "U13") (pin "31") (pinfunction "S7_31") (pintype "bidirectional"))
    )
    (net (code "67") (name "Net-(U13B-S8)") (class "Default")
      (node (ref "JP12") (pin "8") (pinfunction "8_8") (pintype "passive"))
      (node (ref "U13") (pin "32") (pinfunction "S8_32") (pintype "bidirectional"))
    )
    (net (code "68") (name "Net-(U13B-S9)") (class "Default")
      (node (ref "JP12") (pin "9") (pinfunction "9_9") (pintype "passive"))
      (node (ref "U13") (pin "33") (pinfunction "S9_33") (pintype "bidirectional"))
    )
    (net (code "69") (name "Net-(U13B-S10)") (class "Default")
      (node (ref "JP12") (pin "10") (pinfunction "10_10") (pintype "passive"))
      (node (ref "U13") (pin "34") (pinfunction "S10_34") (pintype "bidirectional"))
    )
    (net (code "70") (name "Net-(U13B-S11)") (class "Default")
      (node (ref "JP16") (pin "1") (pinfunction "1_1") (pintype "passive"))
      (node (ref "U13") (pin "35") (pinfunction "S11_35") (pintype "bidirectional"))
    )
    (net (code "71") (name "Net-(U13B-S12)") (class "Default")
      (node (ref "JP16") (pin "2") (pinfunction "2_2") (pintype "passive"))
      (node (ref "U13") (pin "36") (pinfunction "S12_36") (pintype "bidirectional"))
    )
    (net (code "72") (name "Net-(U13B-S13)") (class "Default")
      (node (ref "JP16") (pin "3") (pinfunction "3_3") (pintype "passive"))
      (node (ref "U13") (pin "37") (pinfunction "S13_37") (pintype "bidirectional"))
    )
    (net (code "73") (name "Net-(U13B-S14)") (class "Default")
      (node (ref "JP16") (pin "4") (pinfunction "4_4") (pintype "passive"))
      (node (ref "U13") (pin "38") (pinfunction "S14_38") (pintype "bidirectional"))
    )
    (net (code "74") (name "Net-(U13B-S15)") (class "Default")
      (node (ref "JP16") (pin "5") (pinfunction "5_5") (pintype "passive"))
      (node (ref "U13") (pin "39") (pinfunction "S15_39") (pintype "bidirectional"))
    )
    (net (code "75") (name "Net-(U13B-S16)") (class "Default")
      (node (ref "JP16") (pin "6") (pinfunction "6_6") (pintype "passive"))
      (node (ref "U13") (pin "40") (pinfunction "S16_40") (pintype "bidirectional"))
    )
    (net (code "76") (name "Net-(U14A-D)") (class "Default")
      (node (ref "C29") (pin "1") (pinfunction "1_1") (pintype "passive"))
      (node (ref "TP5") (pin "TP") (pinfunction "TP_TP") (pintype "input"))
      (node (ref "U14") (pin "43") (pinfunction "D_43") (pintype "bidirectional"))
      (node (ref "U3") (pin "1") (pinfunction "OUT_1") (pintype "output"))
    )
    (net (code "77") (name "Net-(U14A-S1)") (class "Default")
      (node (ref "JP5") (pin "1") (pinfunction "1_1") (pintype "passive"))
      (node (ref "U14") (pin "12") (pinfunction "S1_12") (pintype "bidirectional"))
    )
    (net (code "78") (name "Net-(U14A-S2)") (class "Default")
      (node (ref "JP5") (pin "2") (pinfunction "2_2") (pintype "passive"))
      (node (ref "U14") (pin "11") (pinfunction "S2_11") (pintype "bidirectional"))
    )
    (net (code "79") (name "Net-(U14A-S3)") (class "Default")
      (node (ref "JP5") (pin "3") (pinfunction "3_3") (pintype "passive"))
      (node (ref "U14") (pin "10") (pinfunction "S3_10") (pintype "bidirectional"))
    )
    (net (code "80") (name "Net-(U14A-S4)") (class "Default")
      (node (ref "JP5") (pin "4") (pinfunction "4_4") (pintype "passive"))
      (node (ref "U14") (pin "9") (pinfunction "S4_9") (pintype "bidirectional"))
    )
    (net (code "81") (name "Net-(U14A-S5)") (class "Default")
      (node (ref "JP5") (pin "5") (pinfunction "5_5") (pintype "passive"))
      (node (ref "U14") (pin "8") (pinfunction "S5_8") (pintype "bidirectional"))
    )
    (net (code "82") (name "Net-(U14A-S6)") (class "Default")
      (node (ref "JP5") (pin "6") (pinfunction "6_6") (pintype "passive"))
      (node (ref "U14") (pin "7") (pinfunction "S6_7") (pintype "bidirectional"))
    )
    (net (code "83") (name "Net-(U14A-S7)") (class "Default")
      (node (ref "JP5") (pin "7") (pinfunction "7_7") (pintype "passive"))
      (node (ref "U14") (pin "6") (pinfunction "S7_6") (pintype "bidirectional"))
    )
    (net (code "84") (name "Net-(U14A-S8)") (class "Default")
      (node (ref "JP5") (pin "8") (pinfunction "8_8") (pintype "passive"))
      (node (ref "U14") (pin "5") (pinfunction "S8_5") (pintype "bidirectional"))
    )
    (net (code "85") (name "Net-(U14A-S9)") (class "Default")
      (node (ref "JP5") (pin "9") (pinfunction "9_9") (pintype "passive"))
      (node (ref "U14") (pin "4") (pinfunction "S9_4") (pintype "bidirectional"))
    )
    (net (code "86") (name "Net-(U14A-S10)") (class "Default")
      (node (ref "JP5") (pin "10") (pinfunction "10_10") (pintype "passive"))
      (node (ref "U14") (pin "3") (pinfunction "S10_3") (pintype "bidirectional"))
    )
    (net (code "87") (name "Net-(U14A-S11)") (class "Default")
      (node (ref "JP13") (pin "1") (pinfunction "1_1") (pintype "passive"))
      (node (ref "U14") (pin "2") (pinfunction "S11_2") (pintype "bidirectional"))
    )
    (net (code "88") (name "Net-(U14A-S12)") (class "Default")
      (node (ref "JP13") (pin "2") (pinfunction "2_2") (pintype "passive"))
      (node (ref "U14") (pin "1") (pinfunction "S12_1") (pintype "bidirectional"))
    )
    (net (code "89") (name "Net-(U14A-S13)") (class "Default")
      (node (ref "JP13") (pin "3") (pinfunction "3_3") (pintype "passive"))
      (node (ref "U14") (pin "48") (pinfunction "S13_48") (pintype "bidirectional"))
    )
    (net (code "90") (name "Net-(U14A-S14)") (class "Default")
      (node (ref "JP13") (pin "4") (pinfunction "4_4") (pintype "passive"))
      (node (ref "U14") (pin "47") (pinfunction "S14_47") (pintype "bidirectional"))
    )
    (net (code "91") (name "Net-(U14A-S15)") (class "Default")
      (node (ref "JP13") (pin "5") (pinfunction "5_5") (pintype "passive"))
      (node (ref "U14") (pin "46") (pinfunction "S15_46") (pintype "bidirectional"))
    )
    (net (code "92") (name "Net-(U14A-S16)") (class "Default")
      (node (ref "JP13") (pin "6") (pinfunction "6_6") (pintype "passive"))
      (node (ref "U14") (pin "45") (pinfunction "S16_45") (pintype "bidirectional"))
    )
    (net (code "93") (name "Net-(U14B-D)") (class "Default")
      (node (ref "C30") (pin "2") (pinfunction "2_2") (pintype "passive"))
      (node (ref "TP6") (pin "TP") (pinfunction "TP_TP") (pintype "input"))
      (node (ref "U14") (pin "41") (pinfunction "D_41") (pintype "bidirectional"))
      (node (ref "U2") (pin "8") (pinfunction "D_8") (pintype "bidirectional"))
    )
    (net (code "94") (name "Net-(U14B-S1)") (class "Default")
      (node (ref "JP6") (pin "1") (pinfunction "1_1") (pintype "passive"))
      (node (ref "U14") (pin "25") (pinfunction "S1_25") (pintype "bidirectional"))
    )
    (net (code "95") (name "Net-(U14B-S2)") (class "Default")
      (node (ref "JP6") (pin "2") (pinfunction "2_2") (pintype "passive"))
      (node (ref "U14") (pin "26") (pinfunction "S2_26") (pintype "bidirectional"))
    )
    (net (code "96") (name "Net-(U14B-S3)") (class "Default")
      (node (ref "JP6") (pin "3") (pinfunction "3_3") (pintype "passive"))
      (node (ref "U14") (pin "27") (pinfunction "S3_27") (pintype "bidirectional"))
    )
    (net (code "97") (name "Net-(U14B-S4)") (class "Default")
      (node (ref "JP6") (pin "4") (pinfunction "4_4") (pintype "passive"))
      (node (ref "U14") (pin "28") (pinfunction "S4_28") (pintype "bidirectional"))
    )
    (net (code "98") (name "Net-(U14B-S5)") (class "Default")
      (node (ref "JP6") (pin "5") (pinfunction "5_5") (pintype "passive"))
      (node (ref "U14") (pin "29") (pinfunction "S5_29") (pintype "bidirectional"))
    )
    (net (code "99") (name "Net-(U14B-S6)") (class "Default")
      (node (ref "JP6") (pin "6") (pinfunction "6_6") (pintype "passive"))
      (node (ref "U14") (pin "30") (pinfunction "S6_30") (pintype "bidirectional"))
    )
    (net (code "100") (name "Net-(U14B-S7)") (class "Default")
      (node (ref "JP6") (pin "7") (pinfunction "7_7") (pintype "passive"))
      (node (ref "U14") (pin "31") (pinfunction "S7_31") (pintype "bidirectional"))
    )
    (net (code "101") (name "Net-(U14B-S8)") (class "Default")
      (node (ref "JP6") (pin "8") (pinfunction "8_8") (pintype "passive"))
      (node (ref "U14") (pin "32") (pinfunction "S8_32") (pintype "bidirectional"))
    )
    (net (code "102") (name "Net-(U14B-S9)") (class "Default")
      (node (ref "JP6") (pin "9") (pinfunction "9_9") (pintype "passive"))
      (node (ref "U14") (pin "33") (pinfunction "S9_33") (pintype "bidirectional"))
    )
    (net (code "103") (name "Net-(U14B-S10)") (class "Default")
      (node (ref "JP6") (pin "10") (pinfunction "10_10") (pintype "passive"))
      (node (ref "U14") (pin "34") (pinfunction "S10_34") (pintype "bidirectional"))
    )
    (net (code "104") (name "Net-(U14B-S11)") (class "Default")
      (node (ref "JP14") (pin "1") (pinfunction "1_1") (pintype "passive"))
      (node (ref "U14") (pin "35") (pinfunction "S11_35") (pintype "bidirectional"))
    )
    (net (code "105") (name "Net-(U14B-S12)") (class "Default")
      (node (ref "JP14") (pin "2") (pinfunction "2_2") (pintype "passive"))
      (node (ref "U14") (pin "36") (pinfunction "S12_36") (pintype "bidirectional"))
    )
    (net (code "106") (name "Net-(U14B-S13)") (class "Default")
      (node (ref "JP14") (pin "3") (pinfunction "3_3") (pintype "passive"))
      (node (ref "U14") (pin "37") (pinfunction "S13_37") (pintype "bidirectional"))
    )
    (net (code "107") (name "Net-(U14B-S14)") (class "Default")
      (node (ref "JP14") (pin "4") (pinfunction "4_4") (pintype "passive"))
      (node (ref "U14") (pin "38") (pinfunction "S14_38") (pintype "bidirectional"))
    )
    (net (code "108") (name "Net-(U14B-S15)") (class "Default")
      (node (ref "JP14") (pin "5") (pinfunction "5_5") (pintype "passive"))
      (node (ref "U14") (pin "39") (pinfunction "S15_39") (pintype "bidirectional"))
    )
    (net (code "109") (name "Net-(U14B-S16)") (class "Default")
      (node (ref "JP14") (pin "6") (pinfunction "6_6") (pintype "passive"))
      (node (ref "U14") (pin "40") (pinfunction "S16_40") (pintype "bidirectional"))
    )
    (net (code "110") (name "Net-(U15-D)") (class "Default")
      (node (ref "C25") (pin "1") (pinfunction "1_1") (pintype "passive"))
      (node (ref "U15") (pin "5") (pinfunction "D_5") (pintype "bidirectional"))
    )
    (net (code "111") (name "Net-(U15-S1)") (class "Default")
      (node (ref "R20") (pin "1") (pinfunction "1_1") (pintype "passive"))
      (node (ref "U15") (pin "4") (pinfunction "S1_4") (pintype "bidirectional"))
    )
    (net (code "112") (name "Net-(U15-S2)") (class "Default")
      (node (ref "RA") (pin "2") (pinfunction "2_2") (pintype "passive"))
      (node (ref "TP10") (pin "TP") (pinfunction "TP_TP") (pintype "input"))
      (node (ref "U15") (pin "6") (pinfunction "S2_6") (pintype "bidirectional"))
    )
    (net (code "113") (name "PA0") (class "Default")
      (node (ref "JP1") (pin "12") (pinfunction "12_12") (pintype "passive"))
      (node (ref "S1") (pin "1") (pinfunction "0_1") (pintype "passive"))
      (node (ref "S1") (pin "2") (pinfunction "0_2") (pintype "passive"))
    )
    (net (code "114") (name "PA2") (class "Default")
      (node (ref "JP1") (pin "14") (pinfunction "14_14") (pintype "passive"))
      (node (ref "R5") (pin "1") (pinfunction "1_1") (pintype "passive"))
      (node (ref "U6") (pin "30") (pinfunction "MDIO_30") (pintype "bidirectional"))
    )
    (net (code "115") (name "PA7") (class "Default")
      (node (ref "JP1") (pin "17") (pinfunction "17_17") (pintype "passive"))
      (node (ref "RS2") (pin "1") (pinfunction "1_1") (pintype "passive"))
      (node (ref "U6") (pin "40") (pinfunction "CRS_DV_40") (pintype "output"))
    )
    (net (code "116") (name "PA9") (class "Default")
      (node (ref "JP10") (pin "1") (pinfunction "1_1") (pintype "passive"))
      (node (ref "JP2") (pin "44") (pinfunction "44_44") (pintype "passive"))
    )
    (net (code "117") (name "PB4") (class "Default")
      (node (ref "JP2") (pin "25") (pinfunction "25_25") (pintype "passive"))
      (node (ref "U5") (pin "16") (pinfunction "A1_16") (pintype "input"))
    )
    (net (code "118") (name "PB5") (class "Default")
      (node (ref "JP2") (pin "26") (pinfunction "26_26") (pintype "passive"))
      (node (ref "U5") (pin "15") (pinfunction "A2_15") (pintype "input"))
    )
    (net (code "119") (name "PB6") (class "Default")
      (node (ref "JP2") (pin "23") (pinfunction "23_23") (pintype "passive"))
      (node (ref "JP7") (pin "3") (pinfunction "3_3") (pintype "passive"))
      (node (ref "U1") (pin "16") (pinfunction "SCL_16") (pintype "bidirectional"))
      (node (ref "U4") (pin "6") (pinfunction "SCL_6") (pintype "input"))
    )
    (net (code "120") (name "PB7") (class "Default")
      (node (ref "JP2") (pin "24") (pinfunction "24_24") (pintype "passive"))
      (node (ref "U5") (pin "17") (pinfunction "A0_17") (pintype "input"))
    )
    (net (code "121") (name "PB8") (class "Default")
      (node (ref "JP2") (pin "19") (pinfunction "19_19") (pintype "passive"))
      (node (ref "U1") (pin "8") (pinfunction "MCLK_8") (pintype "bidirectional"))
    )
    (net (code "122") (name "PB9") (class "Default")
      (node (ref "JP2") (pin "20") (pinfunction "20_20") (pintype "passive"))
      (node (ref "JP7") (pin "2") (pinfunction "2_2") (pintype "passive"))
      (node (ref "U1") (pin "15") (pinfunction "SDA_15") (pintype "bidirectional"))
      (node (ref "U4") (pin "5") (pinfunction "SDA_5") (pintype "open_collector"))
    )
    (net (code "123") (name "PB11") (class "Default")
      (node (ref "JP1") (pin "35") (pinfunction "35_35") (pintype "passive"))
      (node (ref "U6") (pin "2") (pinfunction "TX_EN_2") (pintype "input"))
    )
    (net (code "124") (name "PB12") (class "Default")
      (node (ref "JP1") (pin "36") (pinfunction "36_36") (pintype "passive"))
      (node (ref "U6") (pin "3") (pinfunction "TXD_0_3") (pintype "input"))
    )
    (net (code "125") (name "PB13") (class "Default")
      (node (ref "JP1") (pin "37") (pinfunction "37_37") (pintype "passive"))
      (node (ref "U6") (pin "4") (pinfunction "TXD_1_4") (pintype "input"))
    )
    (net (code "126") (name "PC1") (class "Default")
      (node (ref "JP1") (pin "7") (pinfunction "7_7") (pintype "passive"))
      (node (ref "U6") (pin "31") (pinfunction "MDC_31") (pintype "input"))
    )
    (net (code "127") (name "PC2") (class "Default")
      (node (ref "JP1") (pin "10") (pinfunction "10_10") (pintype "passive"))
      (node (ref "R18") (pin "2") (pinfunction "2_2") (pintype "passive"))
      (node (ref "RFB1") (pin "2") (pinfunction "2_2") (pintype "passive"))
      (node (ref "RFB2") (pin "2") (pinfunction "2_2") (pintype "passive"))
      (node (ref "RFB3") (pin "2") (pinfunction "2_2") (pintype "passive"))
      (node (ref "RFB4") (pin "2") (pinfunction "2_2") (pintype "passive"))
      (node (ref "RFB5") (pin "2") (pinfunction "2_2") (pintype "passive"))
      (node (ref "RFB6") (pin "2") (pinfunction "2_2") (pintype "passive"))
      (node (ref "RFB7") (pin "2") (pinfunction "2_2") (pintype "passive"))
      (node (ref "RFB8") (pin "2") (pinfunction "2_2") (pintype "passive"))
      (node (ref "TP4") (pin "TP") (pinfunction "TP_TP") (pintype "input"))
      (node (ref "U3") (pin "7") (pinfunction "OUT_7") (pintype "output"))
    )
    (net (code "128") (name "PC4") (class "Default")
      (node (ref "JP1") (pin "20") (pinfunction "20_20") (pintype "passive"))
      (node (ref "U6") (pin "43") (pinfunction "RXD_0_43") (pintype "output"))
    )
    (net (code "129") (name "PC5") (class "Default")
      (node (ref "JP1") (pin "19") (pinfunction "19_19") (pintype "passive"))
      (node (ref "U6") (pin "44") (pinfunction "RXD_1_44") (pintype "output"))
    )
    (net (code "130") (name "PC9") (class "Default")
      (node (ref "JP2") (pin "46") (pinfunction "46_46") (pintype "passive"))
      (node (ref "SJ2") (pin "2") (pinfunction "2_2") (pintype "passive"))
    )
    (net (code "131") (name "PC10") (class "Default")
      (node (ref "JP2") (pin "37") (pinfunction "37_37") (pintype "passive"))
      (node (ref "U11") (pin "6") (pinfunction "SCK_6") (pintype "input"))
      (node (ref "U13") (pin "19") (pinfunction "SCLK_19") (pintype "input"))
      (node (ref "U14") (pin "19") (pinfunction "SCLK_19") (pintype "input"))
      (node (ref "U8") (pin "6") (pinfunction "SCK_6") (pintype "input"))
      (node (ref "U9") (pin "6") (pinfunction "SCK_6") (pintype "input"))
    )
    (net (code "132") (name "PC11") (class "Default")
      (node (ref "JP2") (pin "38") (pinfunction "38_38") (pintype "passive"))
      (node (ref "U11") (pin "2") (pinfunction "SO_2") (pintype "tri_state"))
      (node (ref "U8") (pin "2") (pinfunction "SO_2") (pintype "tri_state"))
      (node (ref "U9") (pin "2") (pinfunction "SO_2") (pintype "tri_state"))
    )
    (net (code "133") (name "PC12") (class "Default")
      (node (ref "JP2") (pin "35") (pinfunction "35_35") (pintype "passive"))
      (node (ref "U11") (pin "5") (pinfunction "SI_5") (pintype "input"))
      (node (ref "U13") (pin "18") (pinfunction "DIN_18") (pintype "input"))
      (node (ref "U14") (pin "18") (pinfunction "DIN_18") (pintype "input"))
      (node (ref "U8") (pin "5") (pinfunction "SI_5") (pintype "input"))
      (node (ref "U9") (pin "5") (pinfunction "SI_5") (pintype "input"))
    )
    (net (code "134") (name "PC15") (class "Default")
      (node (ref "JP2") (pin "10") (pinfunction "10_10") (pintype "passive"))
      (node (ref "U12") (pin "3") (pinfunction "EN_3") (pintype "input"))
    )
    (net (code "135") (name "PD0") (class "Default")
      (node (ref "JP2") (pin "36") (pinfunction "36_36") (pintype "passive"))
      (node (ref "U8") (pin "1") (pinfunction "~{CS}_1") (pintype "input"))
      (node (ref "U9") (pin "1") (pinfunction "~{CS}_1") (pintype "input"))
    )
    (net (code "136") (name "PD1") (class "Default")
      (node (ref "JP2") (pin "33") (pinfunction "33_33") (pintype "passive"))
      (node (ref "U11") (pin "1") (pinfunction "~{CS}_1") (pintype "input"))
    )
    (net (code "137") (name "PD2") (class "Default")
      (node (ref "JP2") (pin "34") (pinfunction "34_34") (pintype "passive"))
      (node (ref "U13") (pin "17") (pinfunction "~{SYNC}_17") (pintype "input"))
      (node (ref "U14") (pin "17") (pinfunction "~{SYNC}_17") (pintype "input"))
    )
    (net (code "138") (name "PD8") (class "Default")
      (node (ref "JP1") (pin "40") (pinfunction "40_40") (pintype "passive"))
      (node (ref "U7") (pin "3") (pinfunction "EN_3") (pintype "input"))
    )
    (net (code "139") (name "PD9") (class "Default")
      (node (ref "JP1") (pin "41") (pinfunction "41_41") (pintype "passive"))
      (node (ref "U7") (pin "4") (pinfunction "~{FAULT}_4") (pintype "output"))
    )
    (net (code "140") (name "PE2") (class "Default")
      (node (ref "J3") (pin "3") (pinfunction "2_3") (pintype "passive"))
      (node (ref "JP2") (pin "15") (pinfunction "15_15") (pintype "passive"))
    )
    (net (code "141") (name "PE4") (class "Default")
      (node (ref "JP2") (pin "13") (pinfunction "13_13") (pintype "passive"))
      (node (ref "U15") (pin "1") (pinfunction "IN_1") (pintype "input"))
    )
    (net (code "142") (name "PE5") (class "Default")
      (node (ref "JP2") (pin "14") (pinfunction "14_14") (pintype "passive"))
      (node (ref "U2") (pin "1") (pinfunction "A0_1") (pintype "input"))
    )
    (net (code "143") (name "PE6") (class "Default")
      (node (ref "JP2") (pin "11") (pinfunction "11_11") (pintype "passive"))
      (node (ref "U2") (pin "10") (pinfunction "A1_10") (pintype "input"))
    )
    (net (code "144") (name "RD_N") (class "Default")
      (node (ref "J2") (pin "6") (pinfunction "RD-_6") (pintype "passive"))
      (node (ref "R4") (pin "1") (pinfunction "1_1") (pintype "passive"))
      (node (ref "U6") (pin "13") (pinfunction "RD-_13") (pintype "bidirectional"))
    )
    (net (code "145") (name "RD_P") (class "Default")
      (node (ref "J2") (pin "4") (pinfunction "RD+_4") (pintype "passive"))
      (node (ref "R3") (pin "1") (pinfunction "1_1") (pintype "passive"))
      (node (ref "U6") (pin "14") (pinfunction "RD+_14") (pintype "bidirectional"))
    )
    (net (code "146") (name "RFB") (class "Default")
      (node (ref "R19") (pin "1") (pinfunction "1_1") (pintype "passive"))
      (node (ref "U1") (pin "4") (pinfunction "RFB_4") (pintype "bidirectional"))
    )
    (net (code "147") (name "TD_N") (class "Default")
      (node (ref "J2") (pin "3") (pinfunction "TD-_3") (pintype "passive"))
      (node (ref "R2") (pin "1") (pinfunction "1_1") (pintype "passive"))
      (node (ref "U6") (pin "16") (pinfunction "TD-_16") (pintype "bidirectional"))
    )
    (net (code "148") (name "TD_P") (class "Default")
      (node (ref "J2") (pin "1") (pinfunction "TD+_1") (pintype "passive"))
      (node (ref "R1") (pin "1") (pinfunction "1_1") (pintype "passive"))
      (node (ref "U6") (pin "17") (pinfunction "TD+_17") (pintype "bidirectional"))
    )
    (net (code "149") (name "USB_N") (class "Default")
      (node (ref "J1") (pin "2") (pinfunction "D-_2") (pintype "passive"))
      (node (ref "JP1") (pin "38") (pinfunction "38_38") (pintype "passive"))
    )
    (net (code "150") (name "USB_P") (class "Default")
      (node (ref "J1") (pin "3") (pinfunction "D+_3") (pintype "passive"))
      (node (ref "JP1") (pin "39") (pinfunction "39_39") (pintype "passive"))
    )
    (net (code "151") (name "VCC") (class "Default")
      (node (ref "C10") (pin "1") (pinfunction "1_1") (pintype "passive"))
      (node (ref "C11") (pin "1") (pinfunction "1_1") (pintype "passive"))
      (node (ref "C12") (pin "1") (pinfunction "1_1") (pintype "passive"))
      (node (ref "C13") (pin "2") (pinfunction "2_2") (pintype "passive"))
      (node (ref "C14") (pin "1") (pinfunction "1_1") (pintype "passive"))
      (node (ref "C22") (pin "1") (pinfunction "1_1") (pintype "passive"))
      (node (ref "C3") (pin "1") (pinfunction "1_1") (pintype "passive"))
      (node (ref "C4") (pin "1") (pinfunction "1_1") (pintype "passive"))
      (node (ref "C5") (pin "1") (pinfunction "1_1") (pintype "passive"))
      (node (ref "C6") (pin "1") (pinfunction "1_1") (pintype "passive"))
      (node (ref "C7") (pin "1") (pinfunction "1_1") (pintype "passive"))
      (node (ref "C8") (pin "1") (pinfunction "1_1") (pintype "passive"))
      (node (ref "C9") (pin "1") (pinfunction "1_1") (pintype "passive"))
      (node (ref "J2") (pin "2") (pinfunction "TCT_2") (pintype "passive"))
      (node (ref "J2") (pin "5") (pinfunction "RCT_5") (pintype "passive"))
      (node (ref "J2") (pin "AG") (pinfunction "AG_AG") (pintype "passive"))
      (node (ref "J2") (pin "AY") (pinfunction "AY_AY") (pintype "passive"))
      (node (ref "JP4") (pin "1") (pinfunction "1_1") (pintype "passive"))
      (node (ref "R1") (pin "2") (pinfunction "2_2") (pintype "passive"))
      (node (ref "R11") (pin "2") (pinfunction "2_2") (pintype "passive"))
      (node (ref "R16") (pin "2") (pinfunction "2_2") (pintype "passive"))
      (node (ref "R2") (pin "2") (pinfunction "2_2") (pintype "passive"))
      (node (ref "R3") (pin "2") (pinfunction "2_2") (pintype "passive"))
      (node (ref "R4") (pin "2") (pinfunction "2_2") (pintype "passive"))
      (node (ref "R5") (pin "2") (pinfunction "2_2") (pintype "passive"))
      (node (ref "R7") (pin "2") (pinfunction "2_2") (pintype "passive"))
      (node (ref "R8") (pin "2") (pinfunction "2_2") (pintype "passive"))
      (node (ref "RS1") (pin "1") (pinfunction "1_1") (pintype "passive"))
      (node (ref "RS3") (pin "1") (pinfunction "1_1") (pintype "passive"))
      (node (ref "RS4") (pin "1") (pinfunction "1_1") (pintype "passive"))
      (node (ref "TP1") (pin "TP") (pinfunction "TP_TP") (pintype "input"))
      (node (ref "U1") (pin "10") (pinfunction "AVDD1_10") (pintype "bidirectional"))
      (node (ref "U1") (pin "11") (pinfunction "AVDD2_11") (pintype "bidirectional"))
      (node (ref "U1") (pin "9") (pinfunction "DVDD_9") (pintype "bidirectional"))
      (node (ref "U11") (pin "7") (pinfunction "VBAT_7") (pintype "power_in"))
      (node (ref "U11") (pin "8") (pinfunction "VDD_8") (pintype "power_in"))
      (node (ref "U13") (pin "13") (pinfunction "VDD_13") (pintype "power_in"))
      (node (ref "U13") (pin "14") (pinfunction "VDD1_14") (pintype "power_in"))
      (node (ref "U14") (pin "13") (pinfunction "VDD_13") (pintype "power_in"))
      (node (ref "U14") (pin "14") (pinfunction "VDD1_14") (pintype "power_in"))
      (node (ref "U15") (pin "2") (pinfunction "VDD_2") (pintype "power_in"))
      (node (ref "U2") (pin "5") (pinfunction "EN_5") (pintype "input"))
      (node (ref "U2") (pin "6") (pinfunction "VDD_6") (pintype "power_in"))
      (node (ref "U3") (pin "8") (pinfunction "V+_8") (pintype "power_in"))
      (node (ref "U4") (pin "8") (pinfunction "VCC_8") (pintype "power_in"))
      (node (ref "U5") (pin "1") (pinfunction "VDD_1") (pintype "power_in"))
      (node (ref "U5") (pin "18") (pinfunction "EN_18") (pintype "input"))
      (node (ref "U6") (pin "22") (pinfunction "AVDD33_22") (pintype "power_in"))
      (node (ref "U6") (pin "32") (pinfunction "IOVDD33__32") (pintype "power_in"))
      (node (ref "U6") (pin "48") (pinfunction "IOVDD33_48") (pintype "power_in"))
      (node (ref "U8") (pin "3") (pinfunction "~{WP}_3") (pintype "input"))
      (node (ref "U8") (pin "7") (pinfunction "~{HOLD}_7") (pintype "input"))
      (node (ref "U8") (pin "8") (pinfunction "VDD_8") (pintype "power_in"))
      (node (ref "U9") (pin "3") (pinfunction "~{WP}_3") (pintype "input"))
      (node (ref "U9") (pin "7") (pinfunction "~{HOLD}_7") (pintype "input"))
      (node (ref "U9") (pin "8") (pinfunction "VDD_8") (pintype "power_in"))
    )
    (net (code "152") (name "VCC{slash}2") (class "Default")
      (node (ref "C26") (pin "2") (pinfunction "2_2") (pintype "passive"))
      (node (ref "R16") (pin "1") (pinfunction "1_1") (pintype "passive"))
      (node (ref "R17") (pin "2") (pinfunction "2_2") (pintype "passive"))
      (node (ref "R20") (pin "2") (pinfunction "2_2") (pintype "passive"))
      (node (ref "TP9") (pin "TP") (pinfunction "TP_TP") (pintype "input"))
      (node (ref "U3") (pin "3") (pinfunction "IN+_3") (pintype "input"))
      (node (ref "U3") (pin "5") (pinfunction "IN+_5") (pintype "input"))
    )
    (net (code "153") (name "VDD") (class "Default")
      (node (ref "JP2") (pin "22") (pinfunction "22_22") (pintype "passive"))
      (node (ref "JP3") (pin "2") (pinfunction "2_2") (pintype "passive"))
      (node (ref "JP7") (pin "4") (pinfunction "4_4") (pintype "passive"))
      (node (ref "S1") (pin "3") (pinfunction "1_3") (pintype "passive"))
      (node (ref "S1") (pin "4") (pinfunction "1_4") (pintype "passive"))
    )
    (net (code "154") (name "VIN") (class "Default")
      (node (ref "R18") (pin "1") (pinfunction "1_1") (pintype "passive"))
      (node (ref "R19") (pin "2") (pinfunction "2_2") (pintype "passive"))
      (node (ref "U1") (pin "5") (pinfunction "VIN_5") (pintype "bidirectional"))
    )
    (net (code "155") (name "VOUT") (class "Default")
      (node (ref "C25") (pin "2") (pinfunction "2_2") (pintype "passive"))
      (node (ref "TP3") (pin "TP") (pinfunction "TP_TP") (pintype "input"))
      (node (ref "U1") (pin "6") (pinfunction "VOUT_6") (pintype "bidirectional"))
    )
    (net (code "156") (name "unconnected-(JP1-Pad3)") (class "Default")
      (node (ref "JP1") (pin "3") (pinfunction "3_3") (pintype "passive"))
    )
    (net (code "157") (name "unconnected-(JP1-Pad4)") (class "Default")
      (node (ref "JP1") (pin "4") (pinfunction "4_4") (pintype "passive"))
    )
    (net (code "158") (name "unconnected-(JP1-Pad5)") (class "Default")
      (node (ref "JP1") (pin "5") (pinfunction "5_5") (pintype "passive"))
    )
    (net (code "159") (name "unconnected-(JP1-Pad8)") (class "Default")
      (node (ref "JP1") (pin "8") (pinfunction "8_8") (pintype "passive"))
    )
    (net (code "160") (name "unconnected-(JP1-Pad9)") (class "Default")
      (node (ref "JP1") (pin "9") (pinfunction "9_9") (pintype "passive"))
    )
    (net (code "161") (name "unconnected-(JP1-Pad13)") (class "Default")
      (node (ref "JP1") (pin "13") (pinfunction "13_13") (pintype "passive"))
    )
    (net (code "162") (name "unconnected-(JP1-Pad15)") (class "Default")
      (node (ref "JP1") (pin "15") (pinfunction "15_15") (pintype "passive"))
    )
    (net (code "163") (name "unconnected-(JP1-Pad16)") (class "Default")
      (node (ref "JP1") (pin "16") (pinfunction "16_16") (pintype "passive"))
    )
    (net (code "164") (name "unconnected-(JP1-Pad18)") (class "Default")
      (node (ref "JP1") (pin "18") (pinfunction "18_18") (pintype "passive"))
    )
    (net (code "165") (name "unconnected-(JP1-Pad21)") (class "Default")
      (node (ref "JP1") (pin "21") (pinfunction "21_21") (pintype "passive"))
    )
    (net (code "166") (name "unconnected-(JP1-Pad22)") (class "Default")
      (node (ref "JP1") (pin "22") (pinfunction "22_22") (pintype "passive"))
    )
    (net (code "167") (name "unconnected-(JP1-Pad23)") (class "Default")
      (node (ref "JP1") (pin "23") (pinfunction "23_23") (pintype "passive"))
    )
    (net (code "168") (name "unconnected-(JP1-Pad24)") (class "Default")
      (node (ref "JP1") (pin "24") (pinfunction "24_24") (pintype "passive"))
    )
    (net (code "169") (name "unconnected-(JP1-Pad25)") (class "Default")
      (node (ref "JP1") (pin "25") (pinfunction "25_25") (pintype "passive"))
    )
    (net (code "170") (name "unconnected-(JP1-Pad26)") (class "Default")
      (node (ref "JP1") (pin "26") (pinfunction "26_26") (pintype "passive"))
    )
    (net (code "171") (name "unconnected-(JP1-Pad27)") (class "Default")
      (node (ref "JP1") (pin "27") (pinfunction "27_27") (pintype "passive"))
    )
    (net (code "172") (name "unconnected-(JP1-Pad28)") (class "Default")
      (node (ref "JP1") (pin "28") (pinfunction "28_28") (pintype "passive"))
    )
    (net (code "173") (name "unconnected-(JP1-Pad29)") (class "Default")
      (node (ref "JP1") (pin "29") (pinfunction "29_29") (pintype "passive"))
    )
    (net (code "174") (name "unconnected-(JP1-Pad30)") (class "Default")
      (node (ref "JP1") (pin "30") (pinfunction "30_30") (pintype "passive"))
    )
    (net (code "175") (name "unconnected-(JP1-Pad31)") (class "Default")
      (node (ref "JP1") (pin "31") (pinfunction "31_31") (pintype "passive"))
    )
    (net (code "176") (name "unconnected-(JP1-Pad32)") (class "Default")
      (node (ref "JP1") (pin "32") (pinfunction "32_32") (pintype "passive"))
    )
    (net (code "177") (name "unconnected-(JP1-Pad33)") (class "Default")
      (node (ref "JP1") (pin "33") (pinfunction "33_33") (pintype "passive"))
    )
    (net (code "178") (name "unconnected-(JP1-Pad34)") (class "Default")
      (node (ref "JP1") (pin "34") (pinfunction "34_34") (pintype "passive"))
    )
    (net (code "179") (name "unconnected-(JP1-Pad42)") (class "Default")
      (node (ref "JP1") (pin "42") (pinfunction "42_42") (pintype "passive"))
    )
    (net (code "180") (name "unconnected-(JP1-Pad43)") (class "Default")
      (node (ref "JP1") (pin "43") (pinfunction "43_43") (pintype "passive"))
    )
    (net (code "181") (name "unconnected-(JP1-Pad44)") (class "Default")
      (node (ref "JP1") (pin "44") (pinfunction "44_44") (pintype "passive"))
    )
    (net (code "182") (name "unconnected-(JP1-Pad45)") (class "Default")
      (node (ref "JP1") (pin "45") (pinfunction "45_45") (pintype "passive"))
    )
    (net (code "183") (name "unconnected-(JP1-Pad46)") (class "Default")
      (node (ref "JP1") (pin "46") (pinfunction "46_46") (pintype "passive"))
    )
    (net (code "184") (name "unconnected-(JP1-Pad47)") (class "Default")
      (node (ref "JP1") (pin "47") (pinfunction "47_47") (pintype "passive"))
    )
    (net (code "185") (name "unconnected-(JP1-Pad48)") (class "Default")
      (node (ref "JP1") (pin "48") (pinfunction "48_48") (pintype "passive"))
    )
    (net (code "186") (name "unconnected-(JP2-Pad7)") (class "Default")
      (node (ref "JP2") (pin "7") (pinfunction "7_7") (pintype "passive"))
    )
    (net (code "187") (name "unconnected-(JP2-Pad8)") (class "Default")
      (node (ref "JP2") (pin "8") (pinfunction "8_8") (pintype "passive"))
    )
    (net (code "188") (name "unconnected-(JP2-Pad9)") (class "Default")
      (node (ref "JP2") (pin "9") (pinfunction "9_9") (pintype "passive"))
    )
    (net (code "189") (name "unconnected-(JP2-Pad12)") (class "Default")
      (node (ref "JP2") (pin "12") (pinfunction "12_12") (pintype "passive"))
    )
    (net (code "190") (name "unconnected-(JP2-Pad16)") (class "Default")
      (node (ref "JP2") (pin "16") (pinfunction "16_16") (pintype "passive"))
    )
    (net (code "191") (name "unconnected-(JP2-Pad17)") (class "Default")
      (node (ref "JP2") (pin "17") (pinfunction "17_17") (pintype "passive"))
    )
    (net (code "192") (name "unconnected-(JP2-Pad18)") (class "Default")
      (node (ref "JP2") (pin "18") (pinfunction "18_18") (pintype "passive"))
    )
    (net (code "193") (name "unconnected-(JP2-Pad21)") (class "Default")
      (node (ref "JP2") (pin "21") (pinfunction "21_21") (pintype "passive"))
    )
    (net (code "194") (name "unconnected-(JP2-Pad27)") (class "Default")
      (node (ref "JP2") (pin "27") (pinfunction "27_27") (pintype "passive"))
    )
    (net (code "195") (name "unconnected-(JP2-Pad28)") (class "Default")
      (node (ref "JP2") (pin "28") (pinfunction "28_28") (pintype "passive"))
    )
    (net (code "196") (name "unconnected-(JP2-Pad29)") (class "Default")
      (node (ref "JP2") (pin "29") (pinfunction "29_29") (pintype "passive"))
    )
    (net (code "197") (name "unconnected-(JP2-Pad30)") (class "Default")
      (node (ref "JP2") (pin "30") (pinfunction "30_30") (pintype "passive"))
    )
    (net (code "198") (name "unconnected-(JP2-Pad31)") (class "Default")
      (node (ref "JP2") (pin "31") (pinfunction "31_31") (pintype "passive"))
    )
    (net (code "199") (name "unconnected-(JP2-Pad32)") (class "Default")
      (node (ref "JP2") (pin "32") (pinfunction "32_32") (pintype "passive"))
    )
    (net (code "200") (name "unconnected-(JP2-Pad39)") (class "Default")
      (node (ref "JP2") (pin "39") (pinfunction "39_39") (pintype "passive"))
    )
    (net (code "201") (name "unconnected-(JP2-Pad40)") (class "Default")
      (node (ref "JP2") (pin "40") (pinfunction "40_40") (pintype "passive"))
    )
    (net (code "202") (name "unconnected-(JP2-Pad41)") (class "Default")
      (node (ref "JP2") (pin "41") (pinfunction "41_41") (pintype "passive"))
    )
    (net (code "203") (name "unconnected-(JP2-Pad42)") (class "Default")
      (node (ref "JP2") (pin "42") (pinfunction "42_42") (pintype "passive"))
    )
    (net (code "204") (name "unconnected-(JP2-Pad43)") (class "Default")
      (node (ref "JP2") (pin "43") (pinfunction "43_43") (pintype "passive"))
    )
    (net (code "205") (name "unconnected-(JP2-Pad45)") (class "Default")
      (node (ref "JP2") (pin "45") (pinfunction "45_45") (pintype "passive"))
    )
    (net (code "206") (name "unconnected-(JP2-Pad47)") (class "Default")
      (node (ref "JP2") (pin "47") (pinfunction "47_47") (pintype "passive"))
    )
    (net (code "207") (name "unconnected-(JP2-Pad48)") (class "Default")
      (node (ref "JP2") (pin "48") (pinfunction "48_48") (pintype "passive"))
    )
    (net (code "208") (name "unconnected-(U5-S9-Pad11)") (class "Default")
      (node (ref "U5") (pin "11") (pinfunction "S9_11") (pintype "bidirectional"))
    )
    (net (code "209") (name "unconnected-(U5-S10-Pad10)") (class "Default")
      (node (ref "U5") (pin "10") (pinfunction "S10_10") (pintype "bidirectional"))
    )
    (net (code "210") (name "unconnected-(U5-S11-Pad9)") (class "Default")
      (node (ref "U5") (pin "9") (pinfunction "S11_9") (pintype "bidirectional"))
    )
    (net (code "211") (name "unconnected-(U5-S12-Pad8)") (class "Default")
      (node (ref "U5") (pin "8") (pinfunction "S12_8") (pintype "bidirectional"))
    )
    (net (code "212") (name "unconnected-(U5-S13-Pad7)") (class "Default")
      (node (ref "U5") (pin "7") (pinfunction "S13_7") (pintype "bidirectional"))
    )
    (net (code "213") (name "unconnected-(U5-S14-Pad6)") (class "Default")
      (node (ref "U5") (pin "6") (pinfunction "S14_6") (pintype "bidirectional"))
    )
    (net (code "214") (name "unconnected-(U5-S15-Pad5)") (class "Default")
      (node (ref "U5") (pin "5") (pinfunction "S15_5") (pintype "bidirectional"))
    )
    (net (code "215") (name "unconnected-(U5-S16-Pad4)") (class "Default")
      (node (ref "U5") (pin "4") (pinfunction "S16_4") (pintype "bidirectional"))
    )
    (net (code "216") (name "unconnected-(U6-COL-Pad42)") (class "Default")
      (node (ref "U6") (pin "42") (pinfunction "COL_42") (pintype "output"))
    )
    (net (code "217") (name "unconnected-(U6-LED_SPEED-Pad27)") (class "Default")
      (node (ref "U6") (pin "27") (pinfunction "LED_SPEED_27") (pintype "output"))
    )
    (net (code "218") (name "unconnected-(U6-PWRDN_INTN-Pad7)") (class "Default")
      (node (ref "U6") (pin "7") (pinfunction "PWRDN_INTN_7") (pintype "bidirectional"))
    )
    (net (code "219") (name "unconnected-(U6-RXD_2-Pad45)") (class "Default")
      (node (ref "U6") (pin "45") (pinfunction "RXD_2_45") (pintype "output"))
    )
    (net (code "220") (name "unconnected-(U6-RXD_3-Pad46)") (class "Default")
      (node (ref "U6") (pin "46") (pinfunction "RXD_3_46") (pintype "output"))
    )
    (net (code "221") (name "unconnected-(U6-RX_CLK-Pad38)") (class "Default")
      (node (ref "U6") (pin "38") (pinfunction "RX_CLK_38") (pintype "output"))
    )
    (net (code "222") (name "unconnected-(U6-RX_ER-Pad41)") (class "Default")
      (node (ref "U6") (pin "41") (pinfunction "RX_ER_41") (pintype "output"))
    )
    (net (code "223") (name "unconnected-(U6-TXD_2-Pad5)") (class "Default")
      (node (ref "U6") (pin "5") (pinfunction "TXD_2_5") (pintype "input"))
    )
    (net (code "224") (name "unconnected-(U6-TXD_3-Pad6)") (class "Default")
      (node (ref "U6") (pin "6") (pinfunction "TXD_3_6") (pintype "input"))
    )
    (net (code "225") (name "unconnected-(U6-TX_CLK-Pad1)") (class "Default")
      (node (ref "U6") (pin "1") (pinfunction "TX_CLK_1") (pintype "output"))
    )
    (net (code "226") (name "unconnected-(U6-X2-Pad33)") (class "Default")
      (node (ref "U6") (pin "33") (pinfunction "X2_33") (pintype "output"))
    )
    (net (code "227") (name "unconnected-(U12-~{FAULT}-Pad4)") (class "Default")
      (node (ref "U12") (pin "4") (pinfunction "~{FAULT}_4") (pintype "output"))
    )
    (net (code "228") (name "~{RST}") (class "Default")
      (node (ref "JP1") (pin "6") (pinfunction "6_6") (pintype "passive"))
      (node (ref "S2") (pin "1") (pinfunction "0_1") (pintype "passive"))
      (node (ref "S2") (pin "2") (pinfunction "0_2") (pintype "passive"))
    )
  )
)
